# Sheet1.net
KiCad netlist of a schematic drawn in Altium Designer
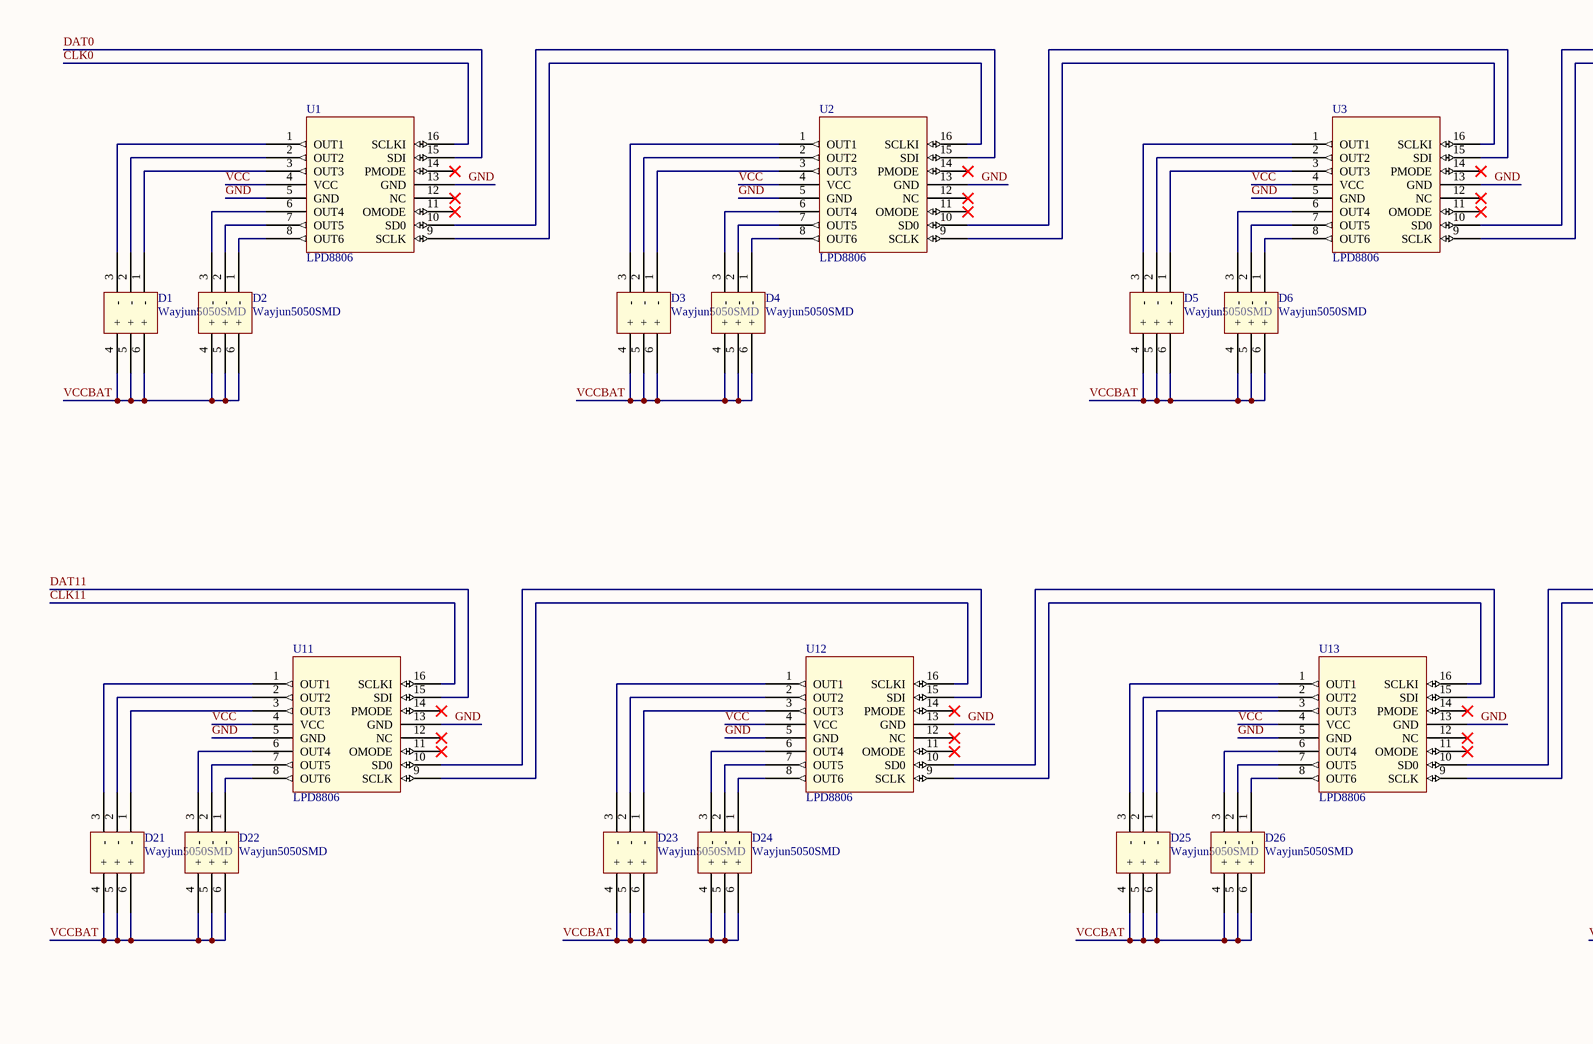
[diagram p0: Sheet1.SchDoc, top left]
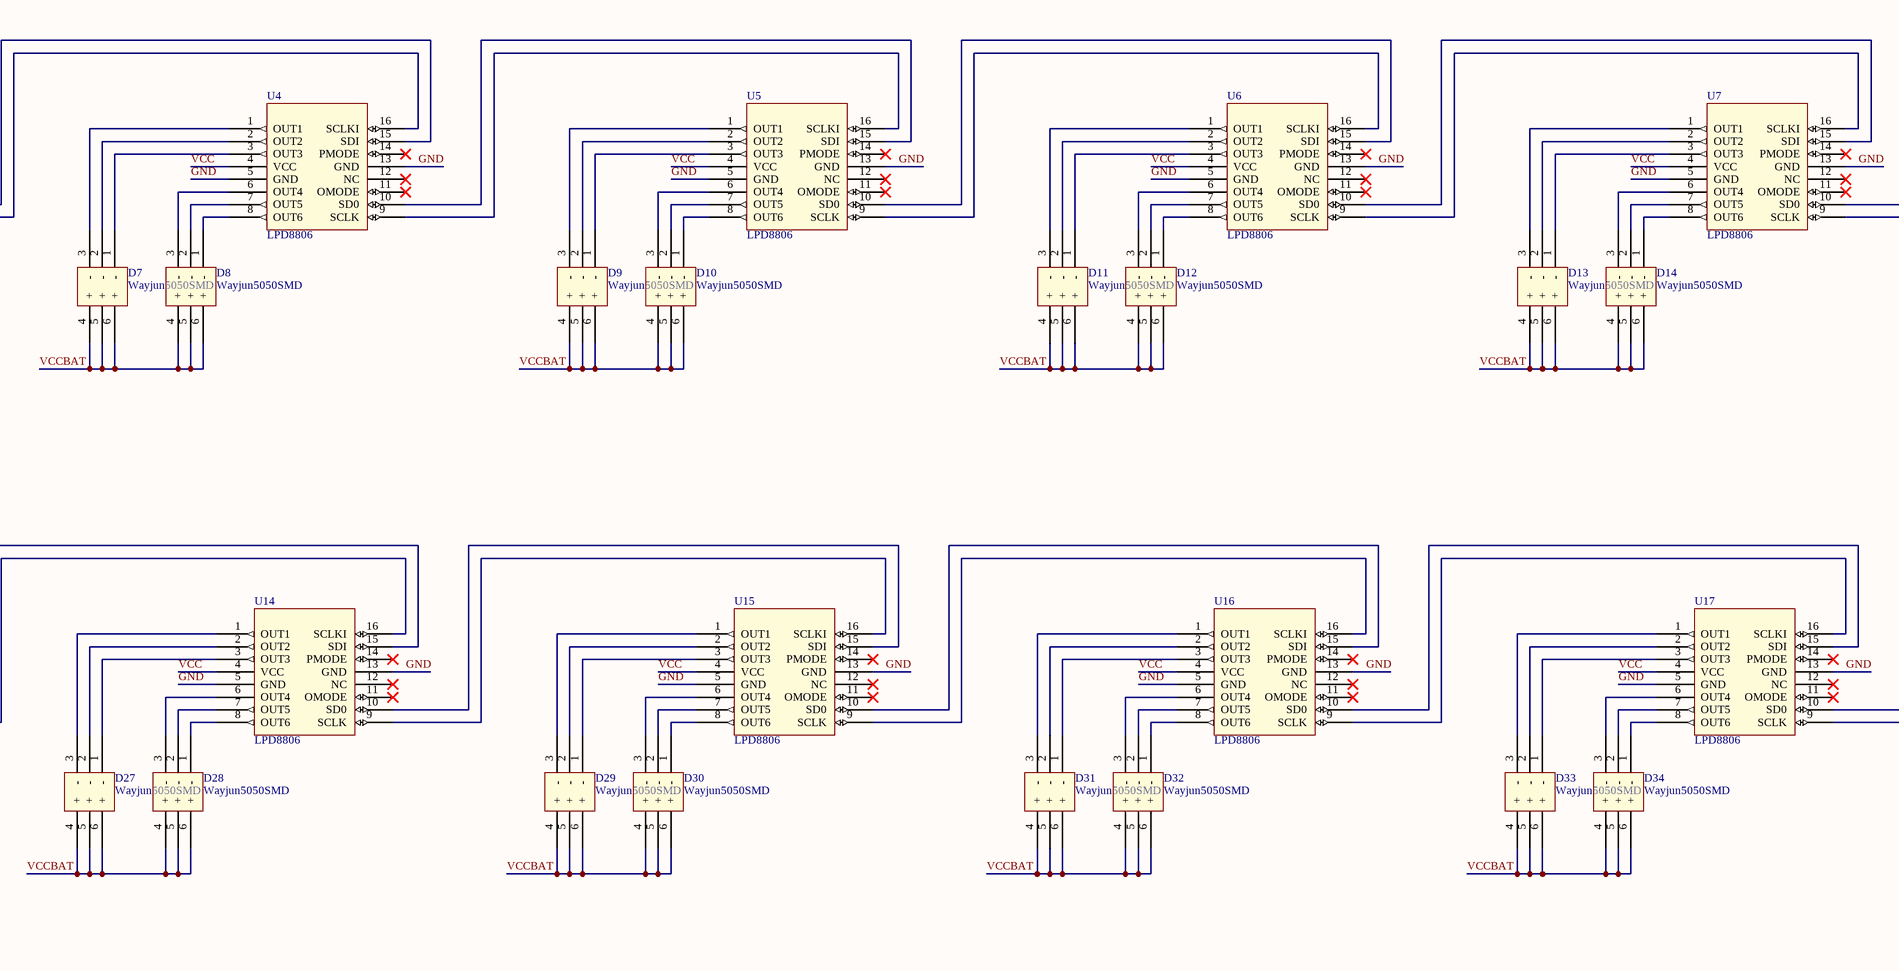
[diagram p1: Sheet1.SchDoc, top middle]
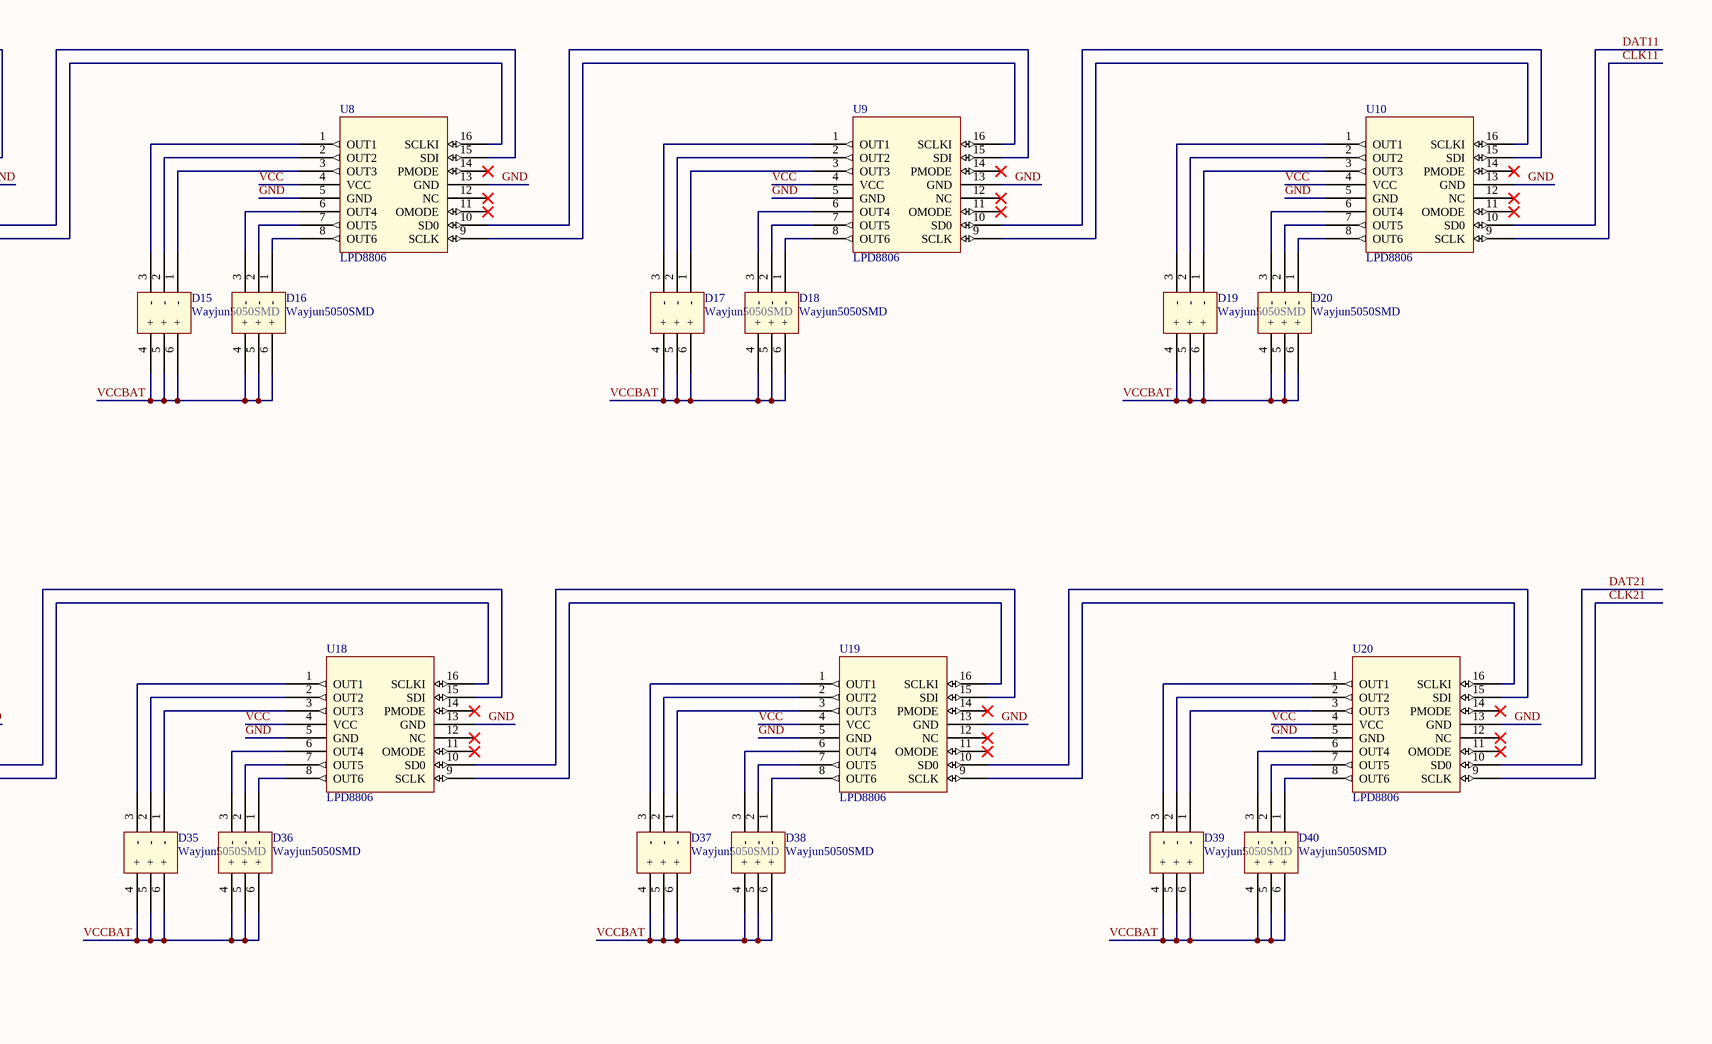
[diagram p2: Sheet1.SchDoc, top right]
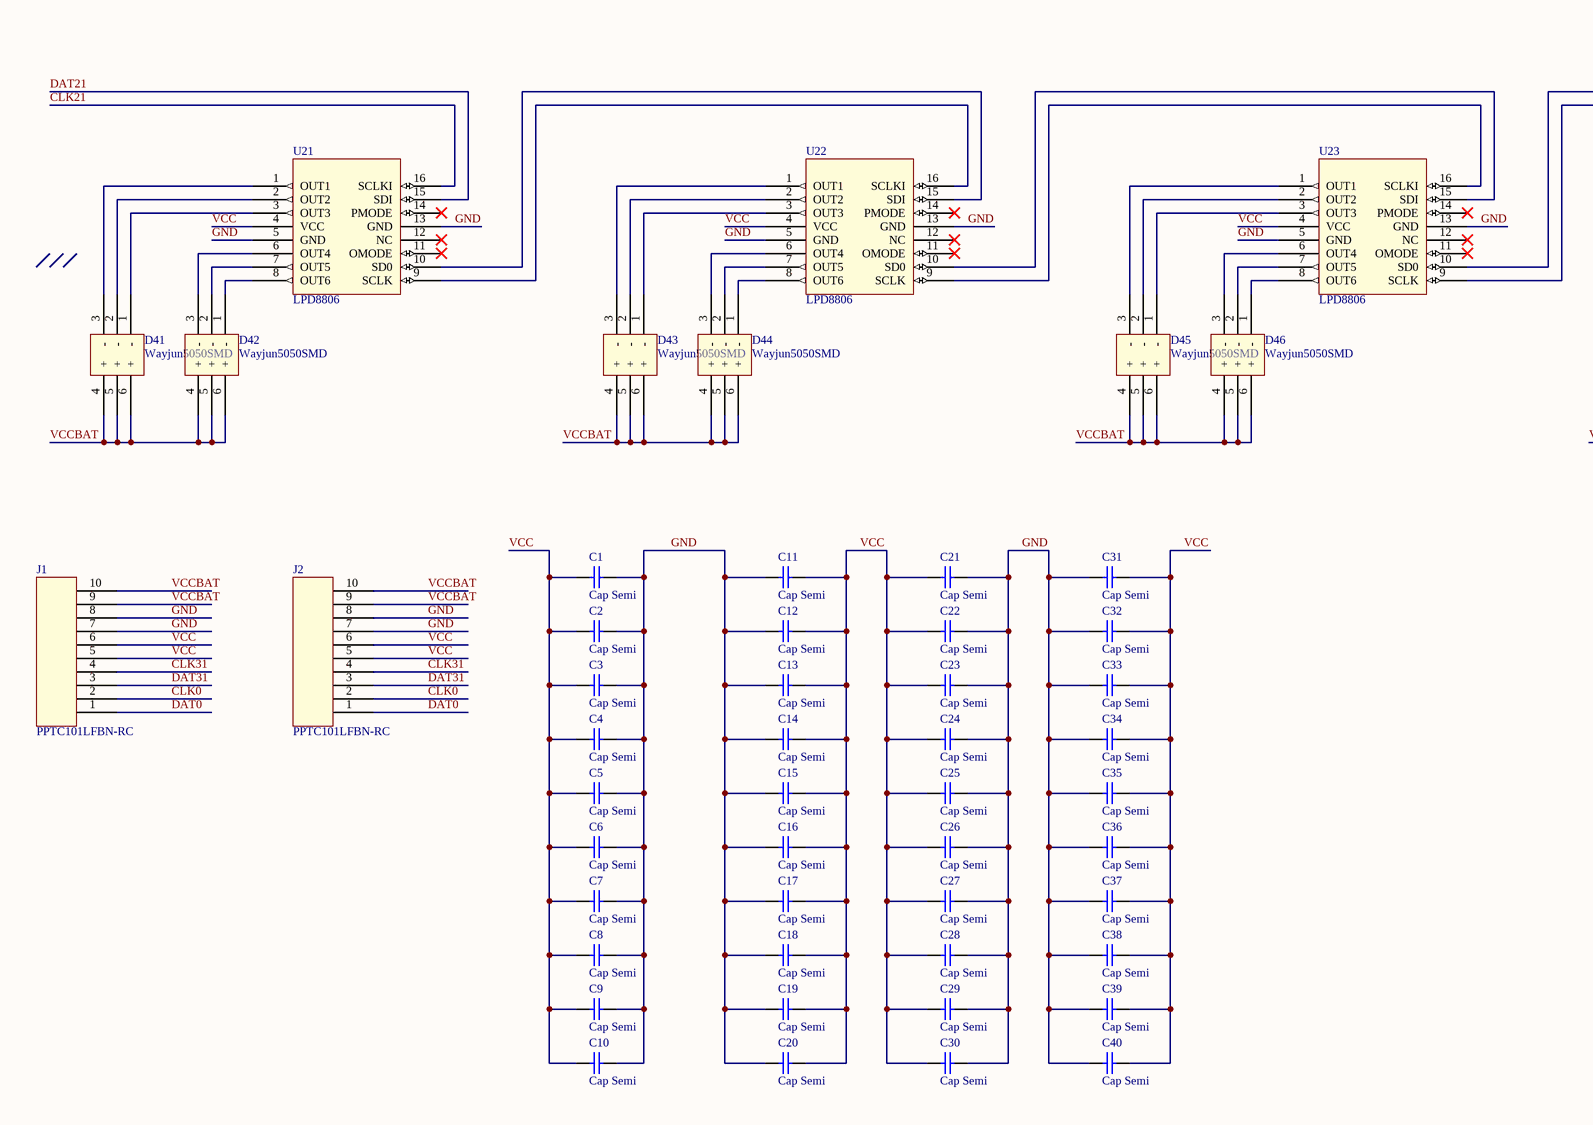
[diagram p3: Sheet1.SchDoc, bottom left]
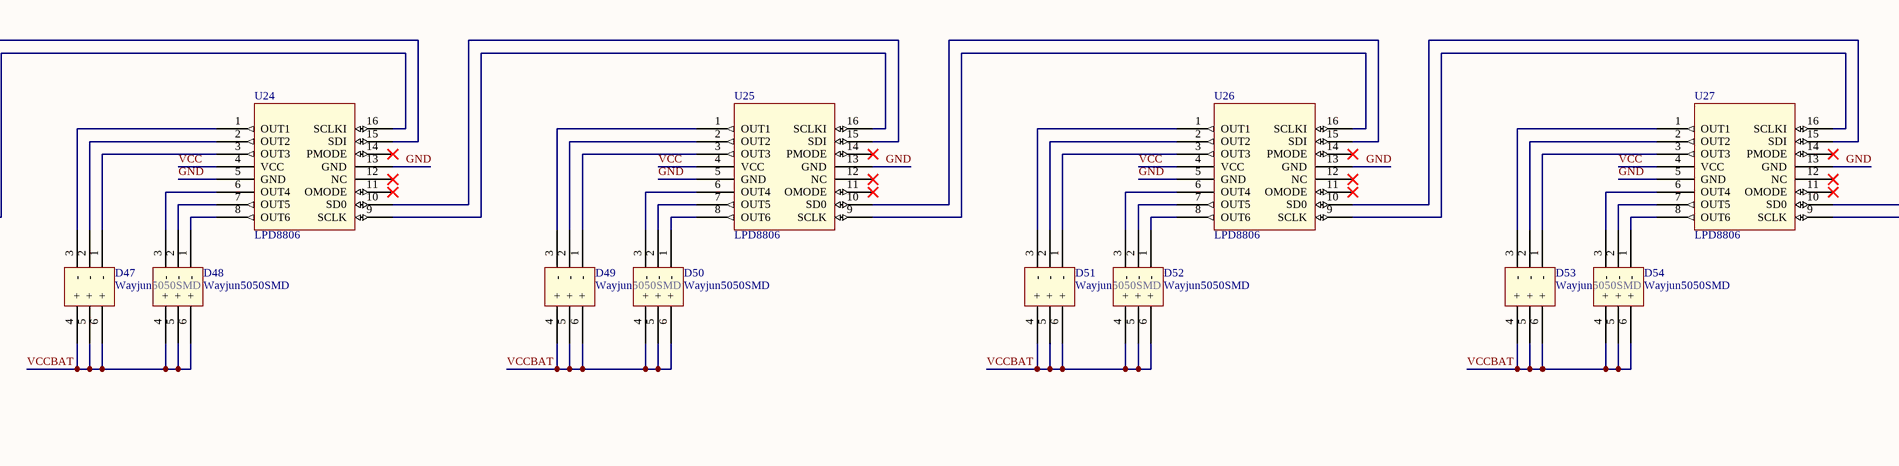
[diagram p4: Sheet1.SchDoc, bottom middle]
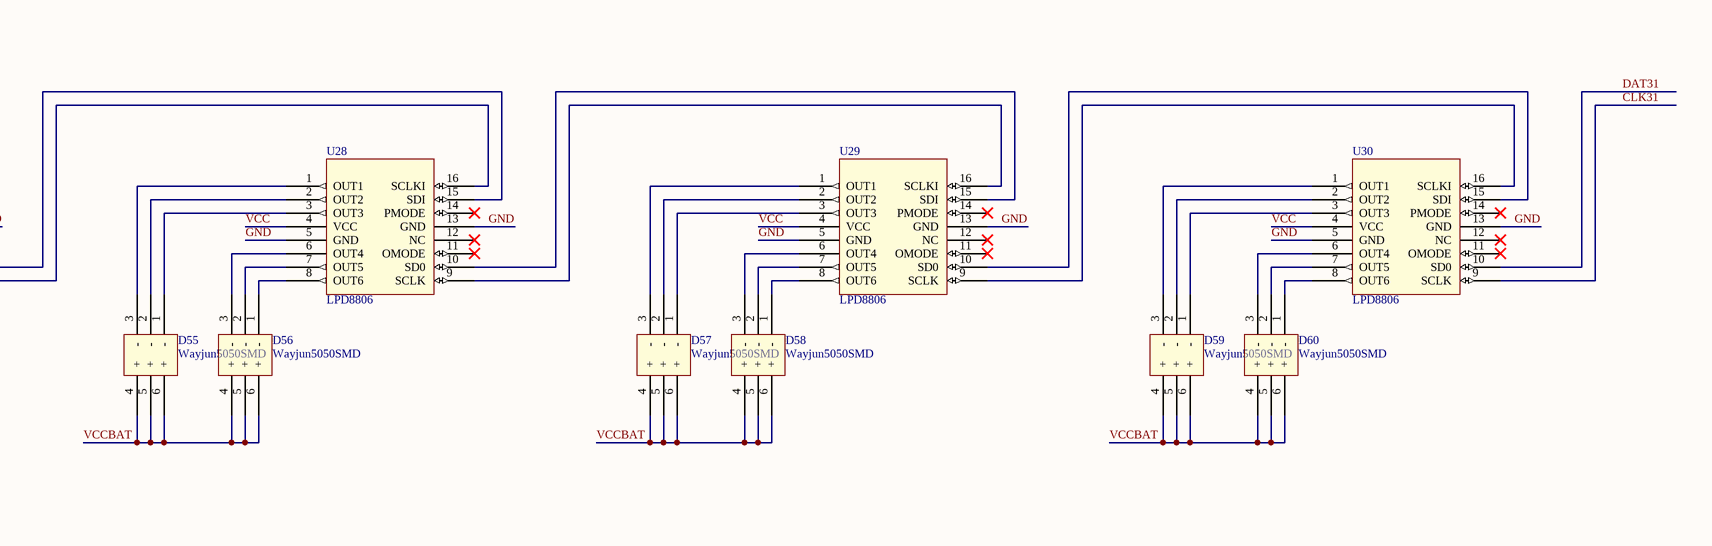
[diagram p5: Sheet1.SchDoc, bottom right]

(export (version "E")
  (design (tool "Eeschema 10.0.6"))
  (components
    (comp (ref "C1")
      (value "Cap Semi")
      (footprint "0402")
      (description "Capacitor (Semiconductor SIM Model)")
      (fields (field (name "PUBLISHER") "Altium Limited"))
      (libsource (lib "Miscellaneous Devices") (part "Cap Semi"))
    )
    (comp (ref "C2")
      (value "Cap Semi")
      (footprint "0402")
      (description "Capacitor (Semiconductor SIM Model)")
      (fields (field (name "PUBLISHER") "Altium Limited"))
      (libsource (lib "Miscellaneous Devices") (part "Cap Semi"))
    )
    (comp (ref "C3")
      (value "Cap Semi")
      (footprint "0402")
      (description "Capacitor (Semiconductor SIM Model)")
      (fields (field (name "PUBLISHER") "Altium Limited"))
      (libsource (lib "Miscellaneous Devices") (part "Cap Semi"))
    )
    (comp (ref "C4")
      (value "Cap Semi")
      (footprint "0402")
      (description "Capacitor (Semiconductor SIM Model)")
      (fields (field (name "PUBLISHER") "Altium Limited"))
      (libsource (lib "Miscellaneous Devices") (part "Cap Semi"))
    )
    (comp (ref "C5")
      (value "Cap Semi")
      (footprint "0402")
      (description "Capacitor (Semiconductor SIM Model)")
      (fields (field (name "PUBLISHER") "Altium Limited"))
      (libsource (lib "Miscellaneous Devices") (part "Cap Semi"))
    )
    (comp (ref "C6")
      (value "Cap Semi")
      (footprint "0402")
      (description "Capacitor (Semiconductor SIM Model)")
      (fields (field (name "PUBLISHER") "Altium Limited"))
      (libsource (lib "Miscellaneous Devices") (part "Cap Semi"))
    )
    (comp (ref "C7")
      (value "Cap Semi")
      (footprint "0402")
      (description "Capacitor (Semiconductor SIM Model)")
      (fields (field (name "PUBLISHER") "Altium Limited"))
      (libsource (lib "Miscellaneous Devices") (part "Cap Semi"))
    )
    (comp (ref "C8")
      (value "Cap Semi")
      (footprint "0402")
      (description "Capacitor (Semiconductor SIM Model)")
      (fields (field (name "PUBLISHER") "Altium Limited"))
      (libsource (lib "Miscellaneous Devices") (part "Cap Semi"))
    )
    (comp (ref "C9")
      (value "Cap Semi")
      (footprint "0402")
      (description "Capacitor (Semiconductor SIM Model)")
      (fields (field (name "PUBLISHER") "Altium Limited"))
      (libsource (lib "Miscellaneous Devices") (part "Cap Semi"))
    )
    (comp (ref "C10")
      (value "Cap Semi")
      (footprint "0402")
      (description "Capacitor (Semiconductor SIM Model)")
      (fields (field (name "PUBLISHER") "Altium Limited"))
      (libsource (lib "Miscellaneous Devices") (part "Cap Semi"))
    )
    (comp (ref "C11")
      (value "Cap Semi")
      (footprint "0402")
      (description "Capacitor (Semiconductor SIM Model)")
      (fields (field (name "PUBLISHER") "Altium Limited"))
      (libsource (lib "Miscellaneous Devices") (part "Cap Semi"))
    )
    (comp (ref "C12")
      (value "Cap Semi")
      (footprint "0402")
      (description "Capacitor (Semiconductor SIM Model)")
      (fields (field (name "PUBLISHER") "Altium Limited"))
      (libsource (lib "Miscellaneous Devices") (part "Cap Semi"))
    )
    (comp (ref "C13")
      (value "Cap Semi")
      (footprint "0402")
      (description "Capacitor (Semiconductor SIM Model)")
      (fields (field (name "PUBLISHER") "Altium Limited"))
      (libsource (lib "Miscellaneous Devices") (part "Cap Semi"))
    )
    (comp (ref "C14")
      (value "Cap Semi")
      (footprint "0402")
      (description "Capacitor (Semiconductor SIM Model)")
      (fields (field (name "PUBLISHER") "Altium Limited"))
      (libsource (lib "Miscellaneous Devices") (part "Cap Semi"))
    )
    (comp (ref "C15")
      (value "Cap Semi")
      (footprint "0402")
      (description "Capacitor (Semiconductor SIM Model)")
      (fields (field (name "PUBLISHER") "Altium Limited"))
      (libsource (lib "Miscellaneous Devices") (part "Cap Semi"))
    )
    (comp (ref "C16")
      (value "Cap Semi")
      (footprint "0402")
      (description "Capacitor (Semiconductor SIM Model)")
      (fields (field (name "PUBLISHER") "Altium Limited"))
      (libsource (lib "Miscellaneous Devices") (part "Cap Semi"))
    )
    (comp (ref "C17")
      (value "Cap Semi")
      (footprint "0402")
      (description "Capacitor (Semiconductor SIM Model)")
      (fields (field (name "PUBLISHER") "Altium Limited"))
      (libsource (lib "Miscellaneous Devices") (part "Cap Semi"))
    )
    (comp (ref "C18")
      (value "Cap Semi")
      (footprint "0402")
      (description "Capacitor (Semiconductor SIM Model)")
      (fields (field (name "PUBLISHER") "Altium Limited"))
      (libsource (lib "Miscellaneous Devices") (part "Cap Semi"))
    )
    (comp (ref "C19")
      (value "Cap Semi")
      (footprint "0402")
      (description "Capacitor (Semiconductor SIM Model)")
      (fields (field (name "PUBLISHER") "Altium Limited"))
      (libsource (lib "Miscellaneous Devices") (part "Cap Semi"))
    )
    (comp (ref "C20")
      (value "Cap Semi")
      (footprint "0402")
      (description "Capacitor (Semiconductor SIM Model)")
      (fields (field (name "PUBLISHER") "Altium Limited"))
      (libsource (lib "Miscellaneous Devices") (part "Cap Semi"))
    )
    (comp (ref "C21")
      (value "Cap Semi")
      (footprint "0402")
      (description "Capacitor (Semiconductor SIM Model)")
      (fields (field (name "PUBLISHER") "Altium Limited"))
      (libsource (lib "Miscellaneous Devices") (part "Cap Semi"))
    )
    (comp (ref "C22")
      (value "Cap Semi")
      (footprint "0402")
      (description "Capacitor (Semiconductor SIM Model)")
      (fields (field (name "PUBLISHER") "Altium Limited"))
      (libsource (lib "Miscellaneous Devices") (part "Cap Semi"))
    )
    (comp (ref "C23")
      (value "Cap Semi")
      (footprint "0402")
      (description "Capacitor (Semiconductor SIM Model)")
      (fields (field (name "PUBLISHER") "Altium Limited"))
      (libsource (lib "Miscellaneous Devices") (part "Cap Semi"))
    )
    (comp (ref "C24")
      (value "Cap Semi")
      (footprint "0402")
      (description "Capacitor (Semiconductor SIM Model)")
      (fields (field (name "PUBLISHER") "Altium Limited"))
      (libsource (lib "Miscellaneous Devices") (part "Cap Semi"))
    )
    (comp (ref "C25")
      (value "Cap Semi")
      (footprint "0402")
      (description "Capacitor (Semiconductor SIM Model)")
      (fields (field (name "PUBLISHER") "Altium Limited"))
      (libsource (lib "Miscellaneous Devices") (part "Cap Semi"))
    )
    (comp (ref "C26")
      (value "Cap Semi")
      (footprint "0402")
      (description "Capacitor (Semiconductor SIM Model)")
      (fields (field (name "PUBLISHER") "Altium Limited"))
      (libsource (lib "Miscellaneous Devices") (part "Cap Semi"))
    )
    (comp (ref "C27")
      (value "Cap Semi")
      (footprint "0402")
      (description "Capacitor (Semiconductor SIM Model)")
      (fields (field (name "PUBLISHER") "Altium Limited"))
      (libsource (lib "Miscellaneous Devices") (part "Cap Semi"))
    )
    (comp (ref "C28")
      (value "Cap Semi")
      (footprint "0402")
      (description "Capacitor (Semiconductor SIM Model)")
      (fields (field (name "PUBLISHER") "Altium Limited"))
      (libsource (lib "Miscellaneous Devices") (part "Cap Semi"))
    )
    (comp (ref "C29")
      (value "Cap Semi")
      (footprint "0402")
      (description "Capacitor (Semiconductor SIM Model)")
      (fields (field (name "PUBLISHER") "Altium Limited"))
      (libsource (lib "Miscellaneous Devices") (part "Cap Semi"))
    )
    (comp (ref "C30")
      (value "Cap Semi")
      (footprint "0402")
      (description "Capacitor (Semiconductor SIM Model)")
      (fields (field (name "PUBLISHER") "Altium Limited"))
      (libsource (lib "Miscellaneous Devices") (part "Cap Semi"))
    )
    (comp (ref "C31")
      (value "Cap Semi")
      (footprint "0402")
      (description "Capacitor (Semiconductor SIM Model)")
      (fields (field (name "PUBLISHER") "Altium Limited"))
      (libsource (lib "Miscellaneous Devices") (part "Cap Semi"))
    )
    (comp (ref "C32")
      (value "Cap Semi")
      (footprint "0402")
      (description "Capacitor (Semiconductor SIM Model)")
      (fields (field (name "PUBLISHER") "Altium Limited"))
      (libsource (lib "Miscellaneous Devices") (part "Cap Semi"))
    )
    (comp (ref "C33")
      (value "Cap Semi")
      (footprint "0402")
      (description "Capacitor (Semiconductor SIM Model)")
      (fields (field (name "PUBLISHER") "Altium Limited"))
      (libsource (lib "Miscellaneous Devices") (part "Cap Semi"))
    )
    (comp (ref "C34")
      (value "Cap Semi")
      (footprint "0402")
      (description "Capacitor (Semiconductor SIM Model)")
      (fields (field (name "PUBLISHER") "Altium Limited"))
      (libsource (lib "Miscellaneous Devices") (part "Cap Semi"))
    )
    (comp (ref "C35")
      (value "Cap Semi")
      (footprint "0402")
      (description "Capacitor (Semiconductor SIM Model)")
      (fields (field (name "PUBLISHER") "Altium Limited"))
      (libsource (lib "Miscellaneous Devices") (part "Cap Semi"))
    )
    (comp (ref "C36")
      (value "Cap Semi")
      (footprint "0402")
      (description "Capacitor (Semiconductor SIM Model)")
      (fields (field (name "PUBLISHER") "Altium Limited"))
      (libsource (lib "Miscellaneous Devices") (part "Cap Semi"))
    )
    (comp (ref "C37")
      (value "Cap Semi")
      (footprint "0402")
      (description "Capacitor (Semiconductor SIM Model)")
      (fields (field (name "PUBLISHER") "Altium Limited"))
      (libsource (lib "Miscellaneous Devices") (part "Cap Semi"))
    )
    (comp (ref "C38")
      (value "Cap Semi")
      (footprint "0402")
      (description "Capacitor (Semiconductor SIM Model)")
      (fields (field (name "PUBLISHER") "Altium Limited"))
      (libsource (lib "Miscellaneous Devices") (part "Cap Semi"))
    )
    (comp (ref "C39")
      (value "Cap Semi")
      (footprint "0402")
      (description "Capacitor (Semiconductor SIM Model)")
      (fields (field (name "PUBLISHER") "Altium Limited"))
      (libsource (lib "Miscellaneous Devices") (part "Cap Semi"))
    )
    (comp (ref "C40")
      (value "Cap Semi")
      (footprint "0402")
      (description "Capacitor (Semiconductor SIM Model)")
      (fields (field (name "PUBLISHER") "Altium Limited"))
      (libsource (lib "Miscellaneous Devices") (part "Cap Semi"))
    )
    (comp (ref "D1")
      (value "Wayjun5050SMD")
      (footprint "SON150P500X150_HS-7N")
      (libsource (lib "lightshow") (part "Wayjun5050SMD"))
    )
    (comp (ref "D2")
      (value "Wayjun5050SMD")
      (footprint "SON150P500X150_HS-7N")
      (libsource (lib "lightshow") (part "Wayjun5050SMD"))
    )
    (comp (ref "D3")
      (value "Wayjun5050SMD")
      (footprint "SON150P500X150_HS-7N")
      (libsource (lib "lightshow") (part "Wayjun5050SMD"))
    )
    (comp (ref "D4")
      (value "Wayjun5050SMD")
      (footprint "SON150P500X150_HS-7N")
      (libsource (lib "lightshow") (part "Wayjun5050SMD"))
    )
    (comp (ref "D5")
      (value "Wayjun5050SMD")
      (footprint "SON150P500X150_HS-7N")
      (libsource (lib "lightshow") (part "Wayjun5050SMD"))
    )
    (comp (ref "D6")
      (value "Wayjun5050SMD")
      (footprint "SON150P500X150_HS-7N")
      (libsource (lib "lightshow") (part "Wayjun5050SMD"))
    )
    (comp (ref "D7")
      (value "Wayjun5050SMD")
      (footprint "SON150P500X150_HS-7N")
      (libsource (lib "lightshow") (part "Wayjun5050SMD"))
    )
    (comp (ref "D8")
      (value "Wayjun5050SMD")
      (footprint "SON150P500X150_HS-7N")
      (libsource (lib "lightshow") (part "Wayjun5050SMD"))
    )
    (comp (ref "D9")
      (value "Wayjun5050SMD")
      (footprint "SON150P500X150_HS-7N")
      (libsource (lib "lightshow") (part "Wayjun5050SMD"))
    )
    (comp (ref "D10")
      (value "Wayjun5050SMD")
      (footprint "SON150P500X150_HS-7N")
      (libsource (lib "lightshow") (part "Wayjun5050SMD"))
    )
    (comp (ref "D11")
      (value "Wayjun5050SMD")
      (footprint "SON150P500X150_HS-7N")
      (libsource (lib "lightshow") (part "Wayjun5050SMD"))
    )
    (comp (ref "D12")
      (value "Wayjun5050SMD")
      (footprint "SON150P500X150_HS-7N")
      (libsource (lib "lightshow") (part "Wayjun5050SMD"))
    )
    (comp (ref "D13")
      (value "Wayjun5050SMD")
      (footprint "SON150P500X150_HS-7N")
      (libsource (lib "lightshow") (part "Wayjun5050SMD"))
    )
    (comp (ref "D14")
      (value "Wayjun5050SMD")
      (footprint "SON150P500X150_HS-7N")
      (libsource (lib "lightshow") (part "Wayjun5050SMD"))
    )
    (comp (ref "D15")
      (value "Wayjun5050SMD")
      (footprint "SON150P500X150_HS-7N")
      (libsource (lib "lightshow") (part "Wayjun5050SMD"))
    )
    (comp (ref "D16")
      (value "Wayjun5050SMD")
      (footprint "SON150P500X150_HS-7N")
      (libsource (lib "lightshow") (part "Wayjun5050SMD"))
    )
    (comp (ref "D17")
      (value "Wayjun5050SMD")
      (footprint "SON150P500X150_HS-7N")
      (libsource (lib "lightshow") (part "Wayjun5050SMD"))
    )
    (comp (ref "D18")
      (value "Wayjun5050SMD")
      (footprint "SON150P500X150_HS-7N")
      (libsource (lib "lightshow") (part "Wayjun5050SMD"))
    )
    (comp (ref "D19")
      (value "Wayjun5050SMD")
      (footprint "SON150P500X150_HS-7N")
      (libsource (lib "lightshow") (part "Wayjun5050SMD"))
    )
    (comp (ref "D20")
      (value "Wayjun5050SMD")
      (footprint "SON150P500X150_HS-7N")
      (libsource (lib "lightshow") (part "Wayjun5050SMD"))
    )
    (comp (ref "D21")
      (value "Wayjun5050SMD")
      (footprint "SON150P500X150_HS-7N")
      (libsource (lib "lightshow") (part "Wayjun5050SMD"))
    )
    (comp (ref "D22")
      (value "Wayjun5050SMD")
      (footprint "SON150P500X150_HS-7N")
      (libsource (lib "lightshow") (part "Wayjun5050SMD"))
    )
    (comp (ref "D23")
      (value "Wayjun5050SMD")
      (footprint "SON150P500X150_HS-7N")
      (libsource (lib "lightshow") (part "Wayjun5050SMD"))
    )
    (comp (ref "D24")
      (value "Wayjun5050SMD")
      (footprint "SON150P500X150_HS-7N")
      (libsource (lib "lightshow") (part "Wayjun5050SMD"))
    )
    (comp (ref "D25")
      (value "Wayjun5050SMD")
      (footprint "SON150P500X150_HS-7N")
      (libsource (lib "lightshow") (part "Wayjun5050SMD"))
    )
    (comp (ref "D26")
      (value "Wayjun5050SMD")
      (footprint "SON150P500X150_HS-7N")
      (libsource (lib "lightshow") (part "Wayjun5050SMD"))
    )
    (comp (ref "D27")
      (value "Wayjun5050SMD")
      (footprint "SON150P500X150_HS-7N")
      (libsource (lib "lightshow") (part "Wayjun5050SMD"))
    )
    (comp (ref "D28")
      (value "Wayjun5050SMD")
      (footprint "SON150P500X150_HS-7N")
      (libsource (lib "lightshow") (part "Wayjun5050SMD"))
    )
    (comp (ref "D29")
      (value "Wayjun5050SMD")
      (footprint "SON150P500X150_HS-7N")
      (libsource (lib "lightshow") (part "Wayjun5050SMD"))
    )
    (comp (ref "D30")
      (value "Wayjun5050SMD")
      (footprint "SON150P500X150_HS-7N")
      (libsource (lib "lightshow") (part "Wayjun5050SMD"))
    )
    (comp (ref "D31")
      (value "Wayjun5050SMD")
      (footprint "SON150P500X150_HS-7N")
      (libsource (lib "lightshow") (part "Wayjun5050SMD"))
    )
    (comp (ref "D32")
      (value "Wayjun5050SMD")
      (footprint "SON150P500X150_HS-7N")
      (libsource (lib "lightshow") (part "Wayjun5050SMD"))
    )
    (comp (ref "D33")
      (value "Wayjun5050SMD")
      (footprint "SON150P500X150_HS-7N")
      (libsource (lib "lightshow") (part "Wayjun5050SMD"))
    )
    (comp (ref "D34")
      (value "Wayjun5050SMD")
      (footprint "SON150P500X150_HS-7N")
      (libsource (lib "lightshow") (part "Wayjun5050SMD"))
    )
    (comp (ref "D35")
      (value "Wayjun5050SMD")
      (footprint "SON150P500X150_HS-7N")
      (libsource (lib "lightshow") (part "Wayjun5050SMD"))
    )
    (comp (ref "D36")
      (value "Wayjun5050SMD")
      (footprint "SON150P500X150_HS-7N")
      (libsource (lib "lightshow") (part "Wayjun5050SMD"))
    )
    (comp (ref "D37")
      (value "Wayjun5050SMD")
      (footprint "SON150P500X150_HS-7N")
      (libsource (lib "lightshow") (part "Wayjun5050SMD"))
    )
    (comp (ref "D38")
      (value "Wayjun5050SMD")
      (footprint "SON150P500X150_HS-7N")
      (libsource (lib "lightshow") (part "Wayjun5050SMD"))
    )
    (comp (ref "D39")
      (value "Wayjun5050SMD")
      (footprint "SON150P500X150_HS-7N")
      (libsource (lib "lightshow") (part "Wayjun5050SMD"))
    )
    (comp (ref "D40")
      (value "Wayjun5050SMD")
      (footprint "SON150P500X150_HS-7N")
      (libsource (lib "lightshow") (part "Wayjun5050SMD"))
    )
    (comp (ref "D41")
      (value "Wayjun5050SMD")
      (footprint "SON150P500X150_HS-7N")
      (libsource (lib "lightshow") (part "Wayjun5050SMD"))
    )
    (comp (ref "D42")
      (value "Wayjun5050SMD")
      (footprint "SON150P500X150_HS-7N")
      (libsource (lib "lightshow") (part "Wayjun5050SMD"))
    )
    (comp (ref "D43")
      (value "Wayjun5050SMD")
      (footprint "SON150P500X150_HS-7N")
      (libsource (lib "lightshow") (part "Wayjun5050SMD"))
    )
    (comp (ref "D44")
      (value "Wayjun5050SMD")
      (footprint "SON150P500X150_HS-7N")
      (libsource (lib "lightshow") (part "Wayjun5050SMD"))
    )
    (comp (ref "D45")
      (value "Wayjun5050SMD")
      (footprint "SON150P500X150_HS-7N")
      (libsource (lib "lightshow") (part "Wayjun5050SMD"))
    )
    (comp (ref "D46")
      (value "Wayjun5050SMD")
      (footprint "SON150P500X150_HS-7N")
      (libsource (lib "lightshow") (part "Wayjun5050SMD"))
    )
    (comp (ref "D47")
      (value "Wayjun5050SMD")
      (footprint "SON150P500X150_HS-7N")
      (libsource (lib "lightshow") (part "Wayjun5050SMD"))
    )
    (comp (ref "D48")
      (value "Wayjun5050SMD")
      (footprint "SON150P500X150_HS-7N")
      (libsource (lib "lightshow") (part "Wayjun5050SMD"))
    )
    (comp (ref "D49")
      (value "Wayjun5050SMD")
      (footprint "SON150P500X150_HS-7N")
      (libsource (lib "lightshow") (part "Wayjun5050SMD"))
    )
    (comp (ref "D50")
      (value "Wayjun5050SMD")
      (footprint "SON150P500X150_HS-7N")
      (libsource (lib "lightshow") (part "Wayjun5050SMD"))
    )
    (comp (ref "D51")
      (value "Wayjun5050SMD")
      (footprint "SON150P500X150_HS-7N")
      (libsource (lib "lightshow") (part "Wayjun5050SMD"))
    )
    (comp (ref "D52")
      (value "Wayjun5050SMD")
      (footprint "SON150P500X150_HS-7N")
      (libsource (lib "lightshow") (part "Wayjun5050SMD"))
    )
    (comp (ref "D53")
      (value "Wayjun5050SMD")
      (footprint "SON150P500X150_HS-7N")
      (libsource (lib "lightshow") (part "Wayjun5050SMD"))
    )
    (comp (ref "D54")
      (value "Wayjun5050SMD")
      (footprint "SON150P500X150_HS-7N")
      (libsource (lib "lightshow") (part "Wayjun5050SMD"))
    )
    (comp (ref "D55")
      (value "Wayjun5050SMD")
      (footprint "SON150P500X150_HS-7N")
      (libsource (lib "lightshow") (part "Wayjun5050SMD"))
    )
    (comp (ref "D56")
      (value "Wayjun5050SMD")
      (footprint "SON150P500X150_HS-7N")
      (libsource (lib "lightshow") (part "Wayjun5050SMD"))
    )
    (comp (ref "D57")
      (value "Wayjun5050SMD")
      (footprint "SON150P500X150_HS-7N")
      (libsource (lib "lightshow") (part "Wayjun5050SMD"))
    )
    (comp (ref "D58")
      (value "Wayjun5050SMD")
      (footprint "SON150P500X150_HS-7N")
      (libsource (lib "lightshow") (part "Wayjun5050SMD"))
    )
    (comp (ref "D59")
      (value "Wayjun5050SMD")
      (footprint "SON150P500X150_HS-7N")
      (libsource (lib "lightshow") (part "Wayjun5050SMD"))
    )
    (comp (ref "D60")
      (value "Wayjun5050SMD")
      (footprint "SON150P500X150_HS-7N")
      (libsource (lib "lightshow") (part "Wayjun5050SMD"))
    )
    (comp (ref "J1")
      (value "PPTC101LFBN-RC")
      (footprint "PPTC101LFBN-RC")
      (description "Sullins PPTC101LFBN-RC 10 Position Header Connector 0.100\" (2.54mm) Through Hole Tin")
      (libsource (lib "lightshow") (part "PPTC101LFBN-RC"))
    )
    (comp (ref "J2")
      (value "PPTC101LFBN-RC")
      (footprint "PPTC101LFBN-RC")
      (description "Sullins PPTC101LFBN-RC 10 Position Header Connector 0.100\" (2.54mm) Through Hole Tin")
      (libsource (lib "lightshow") (part "PPTC101LFBN-RC"))
    )
    (comp (ref "U1")
      (value "LPD8806")
      (footprint "SOP127P600-8N")
      (description "LPD8806 LED Driver")
      (libsource (lib "lightshow") (part "LPD8806"))
    )
    (comp (ref "U2")
      (value "LPD8806")
      (footprint "SOP127P600-8N")
      (description "LPD8806 LED Driver")
      (libsource (lib "lightshow") (part "LPD8806"))
    )
    (comp (ref "U3")
      (value "LPD8806")
      (footprint "SOP127P600-8N")
      (description "LPD8806 LED Driver")
      (libsource (lib "lightshow") (part "LPD8806"))
    )
    (comp (ref "U4")
      (value "LPD8806")
      (footprint "SOP127P600-8N")
      (description "LPD8806 LED Driver")
      (libsource (lib "lightshow") (part "LPD8806"))
    )
    (comp (ref "U5")
      (value "LPD8806")
      (footprint "SOP127P600-8N")
      (description "LPD8806 LED Driver")
      (libsource (lib "lightshow") (part "LPD8806"))
    )
    (comp (ref "U6")
      (value "LPD8806")
      (footprint "SOP127P600-8N")
      (description "LPD8806 LED Driver")
      (libsource (lib "lightshow") (part "LPD8806"))
    )
    (comp (ref "U7")
      (value "LPD8806")
      (footprint "SOP127P600-8N")
      (description "LPD8806 LED Driver")
      (libsource (lib "lightshow") (part "LPD8806"))
    )
    (comp (ref "U8")
      (value "LPD8806")
      (footprint "SOP127P600-8N")
      (description "LPD8806 LED Driver")
      (libsource (lib "lightshow") (part "LPD8806"))
    )
    (comp (ref "U9")
      (value "LPD8806")
      (footprint "SOP127P600-8N")
      (description "LPD8806 LED Driver")
      (libsource (lib "lightshow") (part "LPD8806"))
    )
    (comp (ref "U10")
      (value "LPD8806")
      (footprint "SOP127P600-8N")
      (description "LPD8806 LED Driver")
      (libsource (lib "lightshow") (part "LPD8806"))
    )
    (comp (ref "U11")
      (value "LPD8806")
      (footprint "SOP127P600-8N")
      (description "LPD8806 LED Driver")
      (libsource (lib "lightshow") (part "LPD8806"))
    )
    (comp (ref "U12")
      (value "LPD8806")
      (footprint "SOP127P600-8N")
      (description "LPD8806 LED Driver")
      (libsource (lib "lightshow") (part "LPD8806"))
    )
    (comp (ref "U13")
      (value "LPD8806")
      (footprint "SOP127P600-8N")
      (description "LPD8806 LED Driver")
      (libsource (lib "lightshow") (part "LPD8806"))
    )
    (comp (ref "U14")
      (value "LPD8806")
      (footprint "SOP127P600-8N")
      (description "LPD8806 LED Driver")
      (libsource (lib "lightshow") (part "LPD8806"))
    )
    (comp (ref "U15")
      (value "LPD8806")
      (footprint "SOP127P600-8N")
      (description "LPD8806 LED Driver")
      (libsource (lib "lightshow") (part "LPD8806"))
    )
    (comp (ref "U16")
      (value "LPD8806")
      (footprint "SOP127P600-8N")
      (description "LPD8806 LED Driver")
      (libsource (lib "lightshow") (part "LPD8806"))
    )
    (comp (ref "U17")
      (value "LPD8806")
      (footprint "SOP127P600-8N")
      (description "LPD8806 LED Driver")
      (libsource (lib "lightshow") (part "LPD8806"))
    )
    (comp (ref "U18")
      (value "LPD8806")
      (footprint "SOP127P600-8N")
      (description "LPD8806 LED Driver")
      (libsource (lib "lightshow") (part "LPD8806"))
    )
    (comp (ref "U19")
      (value "LPD8806")
      (footprint "SOP127P600-8N")
      (description "LPD8806 LED Driver")
      (libsource (lib "lightshow") (part "LPD8806"))
    )
    (comp (ref "U20")
      (value "LPD8806")
      (footprint "SOP127P600-8N")
      (description "LPD8806 LED Driver")
      (libsource (lib "lightshow") (part "LPD8806"))
    )
    (comp (ref "U21")
      (value "LPD8806")
      (footprint "SOP127P600-8N")
      (description "LPD8806 LED Driver")
      (libsource (lib "lightshow") (part "LPD8806"))
    )
    (comp (ref "U22")
      (value "LPD8806")
      (footprint "SOP127P600-8N")
      (description "LPD8806 LED Driver")
      (libsource (lib "lightshow") (part "LPD8806"))
    )
    (comp (ref "U23")
      (value "LPD8806")
      (footprint "SOP127P600-8N")
      (description "LPD8806 LED Driver")
      (libsource (lib "lightshow") (part "LPD8806"))
    )
    (comp (ref "U24")
      (value "LPD8806")
      (footprint "SOP127P600-8N")
      (description "LPD8806 LED Driver")
      (libsource (lib "lightshow") (part "LPD8806"))
    )
    (comp (ref "U25")
      (value "LPD8806")
      (footprint "SOP127P600-8N")
      (description "LPD8806 LED Driver")
      (libsource (lib "lightshow") (part "LPD8806"))
    )
    (comp (ref "U26")
      (value "LPD8806")
      (footprint "SOP127P600-8N")
      (description "LPD8806 LED Driver")
      (libsource (lib "lightshow") (part "LPD8806"))
    )
    (comp (ref "U27")
      (value "LPD8806")
      (footprint "SOP127P600-8N")
      (description "LPD8806 LED Driver")
      (libsource (lib "lightshow") (part "LPD8806"))
    )
    (comp (ref "U28")
      (value "LPD8806")
      (footprint "SOP127P600-8N")
      (description "LPD8806 LED Driver")
      (libsource (lib "lightshow") (part "LPD8806"))
    )
    (comp (ref "U29")
      (value "LPD8806")
      (footprint "SOP127P600-8N")
      (description "LPD8806 LED Driver")
      (libsource (lib "lightshow") (part "LPD8806"))
    )
    (comp (ref "U30")
      (value "LPD8806")
      (footprint "SOP127P600-8N")
      (description "LPD8806 LED Driver")
      (libsource (lib "lightshow") (part "LPD8806"))
    )
  )
  (nets
    (net (code "1") (name "/CLK0") (class "Default")
      (node (ref "J1") (pin "2") (pintype "passive"))
      (node (ref "J2") (pin "2") (pintype "passive"))
      (node (ref "U1") (pin "16") (pinfunction "SCLKI_16") (pintype "bidirectional"))
    )
    (net (code "2") (name "/CLK11") (class "Default")
      (node (ref "U10") (pin "9") (pinfunction "SCLK_9") (pintype "bidirectional"))
      (node (ref "U11") (pin "16") (pinfunction "SCLKI_16") (pintype "bidirectional"))
    )
    (net (code "3") (name "/CLK21") (class "Default")
      (node (ref "U20") (pin "9") (pinfunction "SCLK_9") (pintype "bidirectional"))
      (node (ref "U21") (pin "16") (pinfunction "SCLKI_16") (pintype "bidirectional"))
    )
    (net (code "4") (name "/CLK31") (class "Default")
      (node (ref "J1") (pin "4") (pintype "passive"))
      (node (ref "J2") (pin "4") (pintype "passive"))
      (node (ref "U30") (pin "9") (pinfunction "SCLK_9") (pintype "bidirectional"))
    )
    (net (code "5") (name "/DAT0") (class "Default")
      (node (ref "J1") (pin "1") (pintype "passive"))
      (node (ref "J2") (pin "1") (pintype "passive"))
      (node (ref "U1") (pin "15") (pinfunction "SDI_15") (pintype "bidirectional"))
    )
    (net (code "6") (name "/DAT11") (class "Default")
      (node (ref "U10") (pin "10") (pinfunction "SD0_10") (pintype "bidirectional"))
      (node (ref "U11") (pin "15") (pinfunction "SDI_15") (pintype "bidirectional"))
    )
    (net (code "7") (name "/DAT21") (class "Default")
      (node (ref "U20") (pin "10") (pinfunction "SD0_10") (pintype "bidirectional"))
      (node (ref "U21") (pin "15") (pinfunction "SDI_15") (pintype "bidirectional"))
    )
    (net (code "8") (name "/DAT31") (class "Default")
      (node (ref "J1") (pin "3") (pintype "passive"))
      (node (ref "J2") (pin "3") (pintype "passive"))
      (node (ref "U30") (pin "10") (pinfunction "SD0_10") (pintype "bidirectional"))
    )
    (net (code "9") (name "/GND") (class "Default")
      (node (ref "C1") (pin "2") (pinfunction "2_2") (pintype "passive"))
      (node (ref "C10") (pin "2") (pinfunction "2_2") (pintype "passive"))
      (node (ref "C11") (pin "1") (pinfunction "1_1") (pintype "passive"))
      (node (ref "C12") (pin "1") (pinfunction "1_1") (pintype "passive"))
      (node (ref "C13") (pin "1") (pinfunction "1_1") (pintype "passive"))
      (node (ref "C14") (pin "1") (pinfunction "1_1") (pintype "passive"))
      (node (ref "C15") (pin "1") (pinfunction "1_1") (pintype "passive"))
      (node (ref "C16") (pin "1") (pinfunction "1_1") (pintype "passive"))
      (node (ref "C17") (pin "1") (pinfunction "1_1") (pintype "passive"))
      (node (ref "C18") (pin "1") (pinfunction "1_1") (pintype "passive"))
      (node (ref "C19") (pin "1") (pinfunction "1_1") (pintype "passive"))
      (node (ref "C2") (pin "2") (pinfunction "2_2") (pintype "passive"))
      (node (ref "C20") (pin "1") (pinfunction "1_1") (pintype "passive"))
      (node (ref "C21") (pin "2") (pinfunction "2_2") (pintype "passive"))
      (node (ref "C22") (pin "2") (pinfunction "2_2") (pintype "passive"))
      (node (ref "C23") (pin "2") (pinfunction "2_2") (pintype "passive"))
      (node (ref "C24") (pin "2") (pinfunction "2_2") (pintype "passive"))
      (node (ref "C25") (pin "2") (pinfunction "2_2") (pintype "passive"))
      (node (ref "C26") (pin "2") (pinfunction "2_2") (pintype "passive"))
      (node (ref "C27") (pin "2") (pinfunction "2_2") (pintype "passive"))
      (node (ref "C28") (pin "2") (pinfunction "2_2") (pintype "passive"))
      (node (ref "C29") (pin "2") (pinfunction "2_2") (pintype "passive"))
      (node (ref "C3") (pin "2") (pinfunction "2_2") (pintype "passive"))
      (node (ref "C30") (pin "2") (pinfunction "2_2") (pintype "passive"))
      (node (ref "C31") (pin "1") (pinfunction "1_1") (pintype "passive"))
      (node (ref "C32") (pin "1") (pinfunction "1_1") (pintype "passive"))
      (node (ref "C33") (pin "1") (pinfunction "1_1") (pintype "passive"))
      (node (ref "C34") (pin "1") (pinfunction "1_1") (pintype "passive"))
      (node (ref "C35") (pin "1") (pinfunction "1_1") (pintype "passive"))
      (node (ref "C36") (pin "1") (pinfunction "1_1") (pintype "passive"))
      (node (ref "C37") (pin "1") (pinfunction "1_1") (pintype "passive"))
      (node (ref "C38") (pin "1") (pinfunction "1_1") (pintype "passive"))
      (node (ref "C39") (pin "1") (pinfunction "1_1") (pintype "passive"))
      (node (ref "C4") (pin "2") (pinfunction "2_2") (pintype "passive"))
      (node (ref "C40") (pin "1") (pinfunction "1_1") (pintype "passive"))
      (node (ref "C5") (pin "2") (pinfunction "2_2") (pintype "passive"))
      (node (ref "C6") (pin "2") (pinfunction "2_2") (pintype "passive"))
      (node (ref "C7") (pin "2") (pinfunction "2_2") (pintype "passive"))
      (node (ref "C8") (pin "2") (pinfunction "2_2") (pintype "passive"))
      (node (ref "C9") (pin "2") (pinfunction "2_2") (pintype "passive"))
      (node (ref "J1") (pin "7") (pintype "passive"))
      (node (ref "J1") (pin "8") (pintype "passive"))
      (node (ref "J2") (pin "7") (pintype "passive"))
      (node (ref "J2") (pin "8") (pintype "passive"))
      (node (ref "U1") (pin "13") (pinfunction "GND_13") (pintype "power_in"))
      (node (ref "U1") (pin "5") (pinfunction "GND_5") (pintype "power_in"))
      (node (ref "U10") (pin "13") (pinfunction "GND_13") (pintype "power_in"))
      (node (ref "U10") (pin "5") (pinfunction "GND_5") (pintype "power_in"))
      (node (ref "U11") (pin "13") (pinfunction "GND_13") (pintype "power_in"))
      (node (ref "U11") (pin "5") (pinfunction "GND_5") (pintype "power_in"))
      (node (ref "U12") (pin "13") (pinfunction "GND_13") (pintype "power_in"))
      (node (ref "U12") (pin "5") (pinfunction "GND_5") (pintype "power_in"))
      (node (ref "U13") (pin "13") (pinfunction "GND_13") (pintype "power_in"))
      (node (ref "U13") (pin "5") (pinfunction "GND_5") (pintype "power_in"))
      (node (ref "U14") (pin "13") (pinfunction "GND_13") (pintype "power_in"))
      (node (ref "U14") (pin "5") (pinfunction "GND_5") (pintype "power_in"))
      (node (ref "U15") (pin "13") (pinfunction "GND_13") (pintype "power_in"))
      (node (ref "U15") (pin "5") (pinfunction "GND_5") (pintype "power_in"))
      (node (ref "U16") (pin "13") (pinfunction "GND_13") (pintype "power_in"))
      (node (ref "U16") (pin "5") (pinfunction "GND_5") (pintype "power_in"))
      (node (ref "U17") (pin "13") (pinfunction "GND_13") (pintype "power_in"))
      (node (ref "U17") (pin "5") (pinfunction "GND_5") (pintype "power_in"))
      (node (ref "U18") (pin "13") (pinfunction "GND_13") (pintype "power_in"))
      (node (ref "U18") (pin "5") (pinfunction "GND_5") (pintype "power_in"))
      (node (ref "U19") (pin "13") (pinfunction "GND_13") (pintype "power_in"))
      (node (ref "U19") (pin "5") (pinfunction "GND_5") (pintype "power_in"))
      (node (ref "U2") (pin "13") (pinfunction "GND_13") (pintype "power_in"))
      (node (ref "U2") (pin "5") (pinfunction "GND_5") (pintype "power_in"))
      (node (ref "U20") (pin "13") (pinfunction "GND_13") (pintype "power_in"))
      (node (ref "U20") (pin "5") (pinfunction "GND_5") (pintype "power_in"))
      (node (ref "U21") (pin "13") (pinfunction "GND_13") (pintype "power_in"))
      (node (ref "U21") (pin "5") (pinfunction "GND_5") (pintype "power_in"))
      (node (ref "U22") (pin "13") (pinfunction "GND_13") (pintype "power_in"))
      (node (ref "U22") (pin "5") (pinfunction "GND_5") (pintype "power_in"))
      (node (ref "U23") (pin "13") (pinfunction "GND_13") (pintype "power_in"))
      (node (ref "U23") (pin "5") (pinfunction "GND_5") (pintype "power_in"))
      (node (ref "U24") (pin "13") (pinfunction "GND_13") (pintype "power_in"))
      (node (ref "U24") (pin "5") (pinfunction "GND_5") (pintype "power_in"))
      (node (ref "U25") (pin "13") (pinfunction "GND_13") (pintype "power_in"))
      (node (ref "U25") (pin "5") (pinfunction "GND_5") (pintype "power_in"))
      (node (ref "U26") (pin "13") (pinfunction "GND_13") (pintype "power_in"))
      (node (ref "U26") (pin "5") (pinfunction "GND_5") (pintype "power_in"))
      (node (ref "U27") (pin "13") (pinfunction "GND_13") (pintype "power_in"))
      (node (ref "U27") (pin "5") (pinfunction "GND_5") (pintype "power_in"))
      (node (ref "U28") (pin "13") (pinfunction "GND_13") (pintype "power_in"))
      (node (ref "U28") (pin "5") (pinfunction "GND_5") (pintype "power_in"))
      (node (ref "U29") (pin "13") (pinfunction "GND_13") (pintype "power_in"))
      (node (ref "U29") (pin "5") (pinfunction "GND_5") (pintype "power_in"))
      (node (ref "U3") (pin "13") (pinfunction "GND_13") (pintype "power_in"))
      (node (ref "U3") (pin "5") (pinfunction "GND_5") (pintype "power_in"))
      (node (ref "U30") (pin "13") (pinfunction "GND_13") (pintype "power_in"))
      (node (ref "U30") (pin "5") (pinfunction "GND_5") (pintype "power_in"))
      (node (ref "U4") (pin "13") (pinfunction "GND_13") (pintype "power_in"))
      (node (ref "U4") (pin "5") (pinfunction "GND_5") (pintype "power_in"))
      (node (ref "U5") (pin "13") (pinfunction "GND_13") (pintype "power_in"))
      (node (ref "U5") (pin "5") (pinfunction "GND_5") (pintype "power_in"))
      (node (ref "U6") (pin "13") (pinfunction "GND_13") (pintype "power_in"))
      (node (ref "U6") (pin "5") (pinfunction "GND_5") (pintype "power_in"))
      (node (ref "U7") (pin "13") (pinfunction "GND_13") (pintype "power_in"))
      (node (ref "U7") (pin "5") (pinfunction "GND_5") (pintype "power_in"))
      (node (ref "U8") (pin "13") (pinfunction "GND_13") (pintype "power_in"))
      (node (ref "U8") (pin "5") (pinfunction "GND_5") (pintype "power_in"))
      (node (ref "U9") (pin "13") (pinfunction "GND_13") (pintype "power_in"))
      (node (ref "U9") (pin "5") (pinfunction "GND_5") (pintype "power_in"))
    )
    (net (code "10") (name "/VCC") (class "Default")
      (node (ref "C1") (pin "1") (pinfunction "1_1") (pintype "passive"))
      (node (ref "C10") (pin "1") (pinfunction "1_1") (pintype "passive"))
      (node (ref "C11") (pin "2") (pinfunction "2_2") (pintype "passive"))
      (node (ref "C12") (pin "2") (pinfunction "2_2") (pintype "passive"))
      (node (ref "C13") (pin "2") (pinfunction "2_2") (pintype "passive"))
      (node (ref "C14") (pin "2") (pinfunction "2_2") (pintype "passive"))
      (node (ref "C15") (pin "2") (pinfunction "2_2") (pintype "passive"))
      (node (ref "C16") (pin "2") (pinfunction "2_2") (pintype "passive"))
      (node (ref "C17") (pin "2") (pinfunction "2_2") (pintype "passive"))
      (node (ref "C18") (pin "2") (pinfunction "2_2") (pintype "passive"))
      (node (ref "C19") (pin "2") (pinfunction "2_2") (pintype "passive"))
      (node (ref "C2") (pin "1") (pinfunction "1_1") (pintype "passive"))
      (node (ref "C20") (pin "2") (pinfunction "2_2") (pintype "passive"))
      (node (ref "C21") (pin "1") (pinfunction "1_1") (pintype "passive"))
      (node (ref "C22") (pin "1") (pinfunction "1_1") (pintype "passive"))
      (node (ref "C23") (pin "1") (pinfunction "1_1") (pintype "passive"))
      (node (ref "C24") (pin "1") (pinfunction "1_1") (pintype "passive"))
      (node (ref "C25") (pin "1") (pinfunction "1_1") (pintype "passive"))
      (node (ref "C26") (pin "1") (pinfunction "1_1") (pintype "passive"))
      (node (ref "C27") (pin "1") (pinfunction "1_1") (pintype "passive"))
      (node (ref "C28") (pin "1") (pinfunction "1_1") (pintype "passive"))
      (node (ref "C29") (pin "1") (pinfunction "1_1") (pintype "passive"))
      (node (ref "C3") (pin "1") (pinfunction "1_1") (pintype "passive"))
      (node (ref "C30") (pin "1") (pinfunction "1_1") (pintype "passive"))
      (node (ref "C31") (pin "2") (pinfunction "2_2") (pintype "passive"))
      (node (ref "C32") (pin "2") (pinfunction "2_2") (pintype "passive"))
      (node (ref "C33") (pin "2") (pinfunction "2_2") (pintype "passive"))
      (node (ref "C34") (pin "2") (pinfunction "2_2") (pintype "passive"))
      (node (ref "C35") (pin "2") (pinfunction "2_2") (pintype "passive"))
      (node (ref "C36") (pin "2") (pinfunction "2_2") (pintype "passive"))
      (node (ref "C37") (pin "2") (pinfunction "2_2") (pintype "passive"))
      (node (ref "C38") (pin "2") (pinfunction "2_2") (pintype "passive"))
      (node (ref "C39") (pin "2") (pinfunction "2_2") (pintype "passive"))
      (node (ref "C4") (pin "1") (pinfunction "1_1") (pintype "passive"))
      (node (ref "C40") (pin "2") (pinfunction "2_2") (pintype "passive"))
      (node (ref "C5") (pin "1") (pinfunction "1_1") (pintype "passive"))
      (node (ref "C6") (pin "1") (pinfunction "1_1") (pintype "passive"))
      (node (ref "C7") (pin "1") (pinfunction "1_1") (pintype "passive"))
      (node (ref "C8") (pin "1") (pinfunction "1_1") (pintype "passive"))
      (node (ref "C9") (pin "1") (pinfunction "1_1") (pintype "passive"))
      (node (ref "J1") (pin "5") (pintype "passive"))
      (node (ref "J1") (pin "6") (pintype "passive"))
      (node (ref "J2") (pin "5") (pintype "passive"))
      (node (ref "J2") (pin "6") (pintype "passive"))
      (node (ref "U1") (pin "4") (pinfunction "VCC_4") (pintype "power_in"))
      (node (ref "U10") (pin "4") (pinfunction "VCC_4") (pintype "power_in"))
      (node (ref "U11") (pin "4") (pinfunction "VCC_4") (pintype "power_in"))
      (node (ref "U12") (pin "4") (pinfunction "VCC_4") (pintype "power_in"))
      (node (ref "U13") (pin "4") (pinfunction "VCC_4") (pintype "power_in"))
      (node (ref "U14") (pin "4") (pinfunction "VCC_4") (pintype "power_in"))
      (node (ref "U15") (pin "4") (pinfunction "VCC_4") (pintype "power_in"))
      (node (ref "U16") (pin "4") (pinfunction "VCC_4") (pintype "power_in"))
      (node (ref "U17") (pin "4") (pinfunction "VCC_4") (pintype "power_in"))
      (node (ref "U18") (pin "4") (pinfunction "VCC_4") (pintype "power_in"))
      (node (ref "U19") (pin "4") (pinfunction "VCC_4") (pintype "power_in"))
      (node (ref "U2") (pin "4") (pinfunction "VCC_4") (pintype "power_in"))
      (node (ref "U20") (pin "4") (pinfunction "VCC_4") (pintype "power_in"))
      (node (ref "U21") (pin "4") (pinfunction "VCC_4") (pintype "power_in"))
      (node (ref "U22") (pin "4") (pinfunction "VCC_4") (pintype "power_in"))
      (node (ref "U23") (pin "4") (pinfunction "VCC_4") (pintype "power_in"))
      (node (ref "U24") (pin "4") (pinfunction "VCC_4") (pintype "power_in"))
      (node (ref "U25") (pin "4") (pinfunction "VCC_4") (pintype "power_in"))
      (node (ref "U26") (pin "4") (pinfunction "VCC_4") (pintype "power_in"))
      (node (ref "U27") (pin "4") (pinfunction "VCC_4") (pintype "power_in"))
      (node (ref "U28") (pin "4") (pinfunction "VCC_4") (pintype "power_in"))
      (node (ref "U29") (pin "4") (pinfunction "VCC_4") (pintype "power_in"))
      (node (ref "U3") (pin "4") (pinfunction "VCC_4") (pintype "power_in"))
      (node (ref "U30") (pin "4") (pinfunction "VCC_4") (pintype "power_in"))
      (node (ref "U4") (pin "4") (pinfunction "VCC_4") (pintype "power_in"))
      (node (ref "U5") (pin "4") (pinfunction "VCC_4") (pintype "power_in"))
      (node (ref "U6") (pin "4") (pinfunction "VCC_4") (pintype "power_in"))
      (node (ref "U7") (pin "4") (pinfunction "VCC_4") (pintype "power_in"))
      (node (ref "U8") (pin "4") (pinfunction "VCC_4") (pintype "power_in"))
      (node (ref "U9") (pin "4") (pinfunction "VCC_4") (pintype "power_in"))
    )
    (net (code "11") (name "/VCCBAT") (class "Default")
      (node (ref "D1") (pin "4") (pinfunction "+_4") (pintype "power_in"))
      (node (ref "D1") (pin "5") (pinfunction "+_5") (pintype "power_in"))
      (node (ref "D1") (pin "6") (pinfunction "+_6") (pintype "power_in"))
      (node (ref "D10") (pin "4") (pinfunction "+_4") (pintype "power_in"))
      (node (ref "D10") (pin "5") (pinfunction "+_5") (pintype "power_in"))
      (node (ref "D10") (pin "6") (pinfunction "+_6") (pintype "power_in"))
      (node (ref "D11") (pin "4") (pinfunction "+_4") (pintype "power_in"))
      (node (ref "D11") (pin "5") (pinfunction "+_5") (pintype "power_in"))
      (node (ref "D11") (pin "6") (pinfunction "+_6") (pintype "power_in"))
      (node (ref "D12") (pin "4") (pinfunction "+_4") (pintype "power_in"))
      (node (ref "D12") (pin "5") (pinfunction "+_5") (pintype "power_in"))
      (node (ref "D12") (pin "6") (pinfunction "+_6") (pintype "power_in"))
      (node (ref "D13") (pin "4") (pinfunction "+_4") (pintype "power_in"))
      (node (ref "D13") (pin "5") (pinfunction "+_5") (pintype "power_in"))
      (node (ref "D13") (pin "6") (pinfunction "+_6") (pintype "power_in"))
      (node (ref "D14") (pin "4") (pinfunction "+_4") (pintype "power_in"))
      (node (ref "D14") (pin "5") (pinfunction "+_5") (pintype "power_in"))
      (node (ref "D14") (pin "6") (pinfunction "+_6") (pintype "power_in"))
      (node (ref "D15") (pin "4") (pinfunction "+_4") (pintype "power_in"))
      (node (ref "D15") (pin "5") (pinfunction "+_5") (pintype "power_in"))
      (node (ref "D15") (pin "6") (pinfunction "+_6") (pintype "power_in"))
      (node (ref "D16") (pin "4") (pinfunction "+_4") (pintype "power_in"))
      (node (ref "D16") (pin "5") (pinfunction "+_5") (pintype "power_in"))
      (node (ref "D16") (pin "6") (pinfunction "+_6") (pintype "power_in"))
      (node (ref "D17") (pin "4") (pinfunction "+_4") (pintype "power_in"))
      (node (ref "D17") (pin "5") (pinfunction "+_5") (pintype "power_in"))
      (node (ref "D17") (pin "6") (pinfunction "+_6") (pintype "power_in"))
      (node (ref "D18") (pin "4") (pinfunction "+_4") (pintype "power_in"))
      (node (ref "D18") (pin "5") (pinfunction "+_5") (pintype "power_in"))
      (node (ref "D18") (pin "6") (pinfunction "+_6") (pintype "power_in"))
      (node (ref "D19") (pin "4") (pinfunction "+_4") (pintype "power_in"))
      (node (ref "D19") (pin "5") (pinfunction "+_5") (pintype "power_in"))
      (node (ref "D19") (pin "6") (pinfunction "+_6") (pintype "power_in"))
      (node (ref "D2") (pin "4") (pinfunction "+_4") (pintype "power_in"))
      (node (ref "D2") (pin "5") (pinfunction "+_5") (pintype "power_in"))
      (node (ref "D2") (pin "6") (pinfunction "+_6") (pintype "power_in"))
      (node (ref "D20") (pin "4") (pinfunction "+_4") (pintype "power_in"))
      (node (ref "D20") (pin "5") (pinfunction "+_5") (pintype "power_in"))
      (node (ref "D20") (pin "6") (pinfunction "+_6") (pintype "power_in"))
      (node (ref "D21") (pin "4") (pinfunction "+_4") (pintype "power_in"))
      (node (ref "D21") (pin "5") (pinfunction "+_5") (pintype "power_in"))
      (node (ref "D21") (pin "6") (pinfunction "+_6") (pintype "power_in"))
      (node (ref "D22") (pin "4") (pinfunction "+_4") (pintype "power_in"))
      (node (ref "D22") (pin "5") (pinfunction "+_5") (pintype "power_in"))
      (node (ref "D22") (pin "6") (pinfunction "+_6") (pintype "power_in"))
      (node (ref "D23") (pin "4") (pinfunction "+_4") (pintype "power_in"))
      (node (ref "D23") (pin "5") (pinfunction "+_5") (pintype "power_in"))
      (node (ref "D23") (pin "6") (pinfunction "+_6") (pintype "power_in"))
      (node (ref "D24") (pin "4") (pinfunction "+_4") (pintype "power_in"))
      (node (ref "D24") (pin "5") (pinfunction "+_5") (pintype "power_in"))
      (node (ref "D24") (pin "6") (pinfunction "+_6") (pintype "power_in"))
      (node (ref "D25") (pin "4") (pinfunction "+_4") (pintype "power_in"))
      (node (ref "D25") (pin "5") (pinfunction "+_5") (pintype "power_in"))
      (node (ref "D25") (pin "6") (pinfunction "+_6") (pintype "power_in"))
      (node (ref "D26") (pin "4") (pinfunction "+_4") (pintype "power_in"))
      (node (ref "D26") (pin "5") (pinfunction "+_5") (pintype "power_in"))
      (node (ref "D26") (pin "6") (pinfunction "+_6") (pintype "power_in"))
      (node (ref "D27") (pin "4") (pinfunction "+_4") (pintype "power_in"))
      (node (ref "D27") (pin "5") (pinfunction "+_5") (pintype "power_in"))
      (node (ref "D27") (pin "6") (pinfunction "+_6") (pintype "power_in"))
      (node (ref "D28") (pin "4") (pinfunction "+_4") (pintype "power_in"))
      (node (ref "D28") (pin "5") (pinfunction "+_5") (pintype "power_in"))
      (node (ref "D28") (pin "6") (pinfunction "+_6") (pintype "power_in"))
      (node (ref "D29") (pin "4") (pinfunction "+_4") (pintype "power_in"))
      (node (ref "D29") (pin "5") (pinfunction "+_5") (pintype "power_in"))
      (node (ref "D29") (pin "6") (pinfunction "+_6") (pintype "power_in"))
      (node (ref "D3") (pin "4") (pinfunction "+_4") (pintype "power_in"))
      (node (ref "D3") (pin "5") (pinfunction "+_5") (pintype "power_in"))
      (node (ref "D3") (pin "6") (pinfunction "+_6") (pintype "power_in"))
      (node (ref "D30") (pin "4") (pinfunction "+_4") (pintype "power_in"))
      (node (ref "D30") (pin "5") (pinfunction "+_5") (pintype "power_in"))
      (node (ref "D30") (pin "6") (pinfunction "+_6") (pintype "power_in"))
      (node (ref "D31") (pin "4") (pinfunction "+_4") (pintype "power_in"))
      (node (ref "D31") (pin "5") (pinfunction "+_5") (pintype "power_in"))
      (node (ref "D31") (pin "6") (pinfunction "+_6") (pintype "power_in"))
      (node (ref "D32") (pin "4") (pinfunction "+_4") (pintype "power_in"))
      (node (ref "D32") (pin "5") (pinfunction "+_5") (pintype "power_in"))
      (node (ref "D32") (pin "6") (pinfunction "+_6") (pintype "power_in"))
      (node (ref "D33") (pin "4") (pinfunction "+_4") (pintype "power_in"))
      (node (ref "D33") (pin "5") (pinfunction "+_5") (pintype "power_in"))
      (node (ref "D33") (pin "6") (pinfunction "+_6") (pintype "power_in"))
      (node (ref "D34") (pin "4") (pinfunction "+_4") (pintype "power_in"))
      (node (ref "D34") (pin "5") (pinfunction "+_5") (pintype "power_in"))
      (node (ref "D34") (pin "6") (pinfunction "+_6") (pintype "power_in"))
      (node (ref "D35") (pin "4") (pinfunction "+_4") (pintype "power_in"))
      (node (ref "D35") (pin "5") (pinfunction "+_5") (pintype "power_in"))
      (node (ref "D35") (pin "6") (pinfunction "+_6") (pintype "power_in"))
      (node (ref "D36") (pin "4") (pinfunction "+_4") (pintype "power_in"))
      (node (ref "D36") (pin "5") (pinfunction "+_5") (pintype "power_in"))
      (node (ref "D36") (pin "6") (pinfunction "+_6") (pintype "power_in"))
      (node (ref "D37") (pin "4") (pinfunction "+_4") (pintype "power_in"))
      (node (ref "D37") (pin "5") (pinfunction "+_5") (pintype "power_in"))
      (node (ref "D37") (pin "6") (pinfunction "+_6") (pintype "power_in"))
      (node (ref "D38") (pin "4") (pinfunction "+_4") (pintype "power_in"))
      (node (ref "D38") (pin "5") (pinfunction "+_5") (pintype "power_in"))
      (node (ref "D38") (pin "6") (pinfunction "+_6") (pintype "power_in"))
      (node (ref "D39") (pin "4") (pinfunction "+_4") (pintype "power_in"))
      (node (ref "D39") (pin "5") (pinfunction "+_5") (pintype "power_in"))
      (node (ref "D39") (pin "6") (pinfunction "+_6") (pintype "power_in"))
      (node (ref "D4") (pin "4") (pinfunction "+_4") (pintype "power_in"))
      (node (ref "D4") (pin "5") (pinfunction "+_5") (pintype "power_in"))
      (node (ref "D4") (pin "6") (pinfunction "+_6") (pintype "power_in"))
      (node (ref "D40") (pin "4") (pinfunction "+_4") (pintype "power_in"))
      (node (ref "D40") (pin "5") (pinfunction "+_5") (pintype "power_in"))
      (node (ref "D40") (pin "6") (pinfunction "+_6") (pintype "power_in"))
      (node (ref "D41") (pin "4") (pinfunction "+_4") (pintype "power_in"))
      (node (ref "D41") (pin "5") (pinfunction "+_5") (pintype "power_in"))
      (node (ref "D41") (pin "6") (pinfunction "+_6") (pintype "power_in"))
      (node (ref "D42") (pin "4") (pinfunction "+_4") (pintype "power_in"))
      (node (ref "D42") (pin "5") (pinfunction "+_5") (pintype "power_in"))
      (node (ref "D42") (pin "6") (pinfunction "+_6") (pintype "power_in"))
      (node (ref "D43") (pin "4") (pinfunction "+_4") (pintype "power_in"))
      (node (ref "D43") (pin "5") (pinfunction "+_5") (pintype "power_in"))
      (node (ref "D43") (pin "6") (pinfunction "+_6") (pintype "power_in"))
      (node (ref "D44") (pin "4") (pinfunction "+_4") (pintype "power_in"))
      (node (ref "D44") (pin "5") (pinfunction "+_5") (pintype "power_in"))
      (node (ref "D44") (pin "6") (pinfunction "+_6") (pintype "power_in"))
      (node (ref "D45") (pin "4") (pinfunction "+_4") (pintype "power_in"))
      (node (ref "D45") (pin "5") (pinfunction "+_5") (pintype "power_in"))
      (node (ref "D45") (pin "6") (pinfunction "+_6") (pintype "power_in"))
      (node (ref "D46") (pin "4") (pinfunction "+_4") (pintype "power_in"))
      (node (ref "D46") (pin "5") (pinfunction "+_5") (pintype "power_in"))
      (node (ref "D46") (pin "6") (pinfunction "+_6") (pintype "power_in"))
      (node (ref "D47") (pin "4") (pinfunction "+_4") (pintype "power_in"))
      (node (ref "D47") (pin "5") (pinfunction "+_5") (pintype "power_in"))
      (node (ref "D47") (pin "6") (pinfunction "+_6") (pintype "power_in"))
      (node (ref "D48") (pin "4") (pinfunction "+_4") (pintype "power_in"))
      (node (ref "D48") (pin "5") (pinfunction "+_5") (pintype "power_in"))
      (node (ref "D48") (pin "6") (pinfunction "+_6") (pintype "power_in"))
      (node (ref "D49") (pin "4") (pinfunction "+_4") (pintype "power_in"))
      (node (ref "D49") (pin "5") (pinfunction "+_5") (pintype "power_in"))
      (node (ref "D49") (pin "6") (pinfunction "+_6") (pintype "power_in"))
      (node (ref "D5") (pin "4") (pinfunction "+_4") (pintype "power_in"))
      (node (ref "D5") (pin "5") (pinfunction "+_5") (pintype "power_in"))
      (node (ref "D5") (pin "6") (pinfunction "+_6") (pintype "power_in"))
      (node (ref "D50") (pin "4") (pinfunction "+_4") (pintype "power_in"))
      (node (ref "D50") (pin "5") (pinfunction "+_5") (pintype "power_in"))
      (node (ref "D50") (pin "6") (pinfunction "+_6") (pintype "power_in"))
      (node (ref "D51") (pin "4") (pinfunction "+_4") (pintype "power_in"))
      (node (ref "D51") (pin "5") (pinfunction "+_5") (pintype "power_in"))
      (node (ref "D51") (pin "6") (pinfunction "+_6") (pintype "power_in"))
      (node (ref "D52") (pin "4") (pinfunction "+_4") (pintype "power_in"))
      (node (ref "D52") (pin "5") (pinfunction "+_5") (pintype "power_in"))
      (node (ref "D52") (pin "6") (pinfunction "+_6") (pintype "power_in"))
      (node (ref "D53") (pin "4") (pinfunction "+_4") (pintype "power_in"))
      (node (ref "D53") (pin "5") (pinfunction "+_5") (pintype "power_in"))
      (node (ref "D53") (pin "6") (pinfunction "+_6") (pintype "power_in"))
      (node (ref "D54") (pin "4") (pinfunction "+_4") (pintype "power_in"))
      (node (ref "D54") (pin "5") (pinfunction "+_5") (pintype "power_in"))
      (node (ref "D54") (pin "6") (pinfunction "+_6") (pintype "power_in"))
      (node (ref "D55") (pin "4") (pinfunction "+_4") (pintype "power_in"))
      (node (ref "D55") (pin "5") (pinfunction "+_5") (pintype "power_in"))
      (node (ref "D55") (pin "6") (pinfunction "+_6") (pintype "power_in"))
      (node (ref "D56") (pin "4") (pinfunction "+_4") (pintype "power_in"))
      (node (ref "D56") (pin "5") (pinfunction "+_5") (pintype "power_in"))
      (node (ref "D56") (pin "6") (pinfunction "+_6") (pintype "power_in"))
      (node (ref "D57") (pin "4") (pinfunction "+_4") (pintype "power_in"))
      (node (ref "D57") (pin "5") (pinfunction "+_5") (pintype "power_in"))
      (node (ref "D57") (pin "6") (pinfunction "+_6") (pintype "power_in"))
      (node (ref "D58") (pin "4") (pinfunction "+_4") (pintype "power_in"))
      (node (ref "D58") (pin "5") (pinfunction "+_5") (pintype "power_in"))
      (node (ref "D58") (pin "6") (pinfunction "+_6") (pintype "power_in"))
      (node (ref "D59") (pin "4") (pinfunction "+_4") (pintype "power_in"))
      (node (ref "D59") (pin "5") (pinfunction "+_5") (pintype "power_in"))
      (node (ref "D59") (pin "6") (pinfunction "+_6") (pintype "power_in"))
      (node (ref "D6") (pin "4") (pinfunction "+_4") (pintype "power_in"))
      (node (ref "D6") (pin "5") (pinfunction "+_5") (pintype "power_in"))
      (node (ref "D6") (pin "6") (pinfunction "+_6") (pintype "power_in"))
      (node (ref "D60") (pin "4") (pinfunction "+_4") (pintype "power_in"))
      (node (ref "D60") (pin "5") (pinfunction "+_5") (pintype "power_in"))
      (node (ref "D60") (pin "6") (pinfunction "+_6") (pintype "power_in"))
      (node (ref "D7") (pin "4") (pinfunction "+_4") (pintype "power_in"))
      (node (ref "D7") (pin "5") (pinfunction "+_5") (pintype "power_in"))
      (node (ref "D7") (pin "6") (pinfunction "+_6") (pintype "power_in"))
      (node (ref "D8") (pin "4") (pinfunction "+_4") (pintype "power_in"))
      (node (ref "D8") (pin "5") (pinfunction "+_5") (pintype "power_in"))
      (node (ref "D8") (pin "6") (pinfunction "+_6") (pintype "power_in"))
      (node (ref "D9") (pin "4") (pinfunction "+_4") (pintype "power_in"))
      (node (ref "D9") (pin "5") (pinfunction "+_5") (pintype "power_in"))
      (node (ref "D9") (pin "6") (pinfunction "+_6") (pintype "power_in"))
      (node (ref "J1") (pin "10") (pintype "passive"))
      (node (ref "J1") (pin "9") (pintype "passive"))
      (node (ref "J2") (pin "10") (pintype "passive"))
      (node (ref "J2") (pin "9") (pintype "passive"))
    )
    (net (code "12") (name "Net-(U1-OUT1)") (class "Default")
      (node (ref "D1") (pin "3") (pinfunction "-_3") (pintype "power_in"))
      (node (ref "U1") (pin "1") (pinfunction "OUT1_1") (pintype "output"))
    )
    (net (code "13") (name "Net-(U1-OUT2)") (class "Default")
      (node (ref "D1") (pin "2") (pinfunction "-_2") (pintype "power_in"))
      (node (ref "U1") (pin "2") (pinfunction "OUT2_2") (pintype "output"))
    )
    (net (code "14") (name "Net-(U1-OUT3)") (class "Default")
      (node (ref "D1") (pin "1") (pinfunction "-_1") (pintype "power_in"))
      (node (ref "U1") (pin "3") (pinfunction "OUT3_3") (pintype "output"))
    )
    (net (code "15") (name "Net-(U1-OUT4)") (class "Default")
      (node (ref "D2") (pin "3") (pinfunction "-_3") (pintype "power_in"))
      (node (ref "U1") (pin "6") (pinfunction "OUT4_6") (pintype "power_in"))
    )
    (net (code "16") (name "Net-(U1-OUT5)") (class "Default")
      (node (ref "D2") (pin "2") (pinfunction "-_2") (pintype "power_in"))
      (node (ref "U1") (pin "7") (pinfunction "OUT5_7") (pintype "output"))
    )
    (net (code "17") (name "Net-(U1-OUT6)") (class "Default")
      (node (ref "D2") (pin "1") (pinfunction "-_1") (pintype "power_in"))
      (node (ref "U1") (pin "8") (pinfunction "OUT6_8") (pintype "output"))
    )
    (net (code "18") (name "Net-(U1-SCLK)") (class "Default")
      (node (ref "U1") (pin "9") (pinfunction "SCLK_9") (pintype "bidirectional"))
      (node (ref "U2") (pin "16") (pinfunction "SCLKI_16") (pintype "bidirectional"))
    )
    (net (code "19") (name "Net-(U1-SD0)") (class "Default")
      (node (ref "U1") (pin "10") (pinfunction "SD0_10") (pintype "bidirectional"))
      (node (ref "U2") (pin "15") (pinfunction "SDI_15") (pintype "bidirectional"))
    )
    (net (code "20") (name "Net-(U2-OUT1)") (class "Default")
      (node (ref "D3") (pin "3") (pinfunction "-_3") (pintype "power_in"))
      (node (ref "U2") (pin "1") (pinfunction "OUT1_1") (pintype "output"))
    )
    (net (code "21") (name "Net-(U2-OUT2)") (class "Default")
      (node (ref "D3") (pin "2") (pinfunction "-_2") (pintype "power_in"))
      (node (ref "U2") (pin "2") (pinfunction "OUT2_2") (pintype "output"))
    )
    (net (code "22") (name "Net-(U2-OUT3)") (class "Default")
      (node (ref "D3") (pin "1") (pinfunction "-_1") (pintype "power_in"))
      (node (ref "U2") (pin "3") (pinfunction "OUT3_3") (pintype "output"))
    )
    (net (code "23") (name "Net-(U2-OUT4)") (class "Default")
      (node (ref "D4") (pin "3") (pinfunction "-_3") (pintype "power_in"))
      (node (ref "U2") (pin "6") (pinfunction "OUT4_6") (pintype "power_in"))
    )
    (net (code "24") (name "Net-(U2-OUT5)") (class "Default")
      (node (ref "D4") (pin "2") (pinfunction "-_2") (pintype "power_in"))
      (node (ref "U2") (pin "7") (pinfunction "OUT5_7") (pintype "output"))
    )
    (net (code "25") (name "Net-(U2-OUT6)") (class "Default")
      (node (ref "D4") (pin "1") (pinfunction "-_1") (pintype "power_in"))
      (node (ref "U2") (pin "8") (pinfunction "OUT6_8") (pintype "output"))
    )
    (net (code "26") (name "Net-(U2-SCLK)") (class "Default")
      (node (ref "U2") (pin "9") (pinfunction "SCLK_9") (pintype "bidirectional"))
      (node (ref "U3") (pin "16") (pinfunction "SCLKI_16") (pintype "bidirectional"))
    )
    (net (code "27") (name "Net-(U2-SD0)") (class "Default")
      (node (ref "U2") (pin "10") (pinfunction "SD0_10") (pintype "bidirectional"))
      (node (ref "U3") (pin "15") (pinfunction "SDI_15") (pintype "bidirectional"))
    )
    (net (code "28") (name "Net-(U3-OUT1)") (class "Default")
      (node (ref "D5") (pin "3") (pinfunction "-_3") (pintype "power_in"))
      (node (ref "U3") (pin "1") (pinfunction "OUT1_1") (pintype "output"))
    )
    (net (code "29") (name "Net-(U3-OUT2)") (class "Default")
      (node (ref "D5") (pin "2") (pinfunction "-_2") (pintype "power_in"))
      (node (ref "U3") (pin "2") (pinfunction "OUT2_2") (pintype "output"))
    )
    (net (code "30") (name "Net-(U3-OUT3)") (class "Default")
      (node (ref "D5") (pin "1") (pinfunction "-_1") (pintype "power_in"))
      (node (ref "U3") (pin "3") (pinfunction "OUT3_3") (pintype "output"))
    )
    (net (code "31") (name "Net-(U3-OUT4)") (class "Default")
      (node (ref "D6") (pin "3") (pinfunction "-_3") (pintype "power_in"))
      (node (ref "U3") (pin "6") (pinfunction "OUT4_6") (pintype "power_in"))
    )
    (net (code "32") (name "Net-(U3-OUT5)") (class "Default")
      (node (ref "D6") (pin "2") (pinfunction "-_2") (pintype "power_in"))
      (node (ref "U3") (pin "7") (pinfunction "OUT5_7") (pintype "output"))
    )
    (net (code "33") (name "Net-(U3-OUT6)") (class "Default")
      (node (ref "D6") (pin "1") (pinfunction "-_1") (pintype "power_in"))
      (node (ref "U3") (pin "8") (pinfunction "OUT6_8") (pintype "output"))
    )
    (net (code "34") (name "Net-(U3-SCLK)") (class "Default")
      (node (ref "U3") (pin "9") (pinfunction "SCLK_9") (pintype "bidirectional"))
      (node (ref "U4") (pin "16") (pinfunction "SCLKI_16") (pintype "bidirectional"))
    )
    (net (code "35") (name "Net-(U3-SD0)") (class "Default")
      (node (ref "U3") (pin "10") (pinfunction "SD0_10") (pintype "bidirectional"))
      (node (ref "U4") (pin "15") (pinfunction "SDI_15") (pintype "bidirectional"))
    )
    (net (code "36") (name "Net-(U4-OUT1)") (class "Default")
      (node (ref "D7") (pin "3") (pinfunction "-_3") (pintype "power_in"))
      (node (ref "U4") (pin "1") (pinfunction "OUT1_1") (pintype "output"))
    )
    (net (code "37") (name "Net-(U4-OUT2)") (class "Default")
      (node (ref "D7") (pin "2") (pinfunction "-_2") (pintype "power_in"))
      (node (ref "U4") (pin "2") (pinfunction "OUT2_2") (pintype "output"))
    )
    (net (code "38") (name "Net-(U4-OUT3)") (class "Default")
      (node (ref "D7") (pin "1") (pinfunction "-_1") (pintype "power_in"))
      (node (ref "U4") (pin "3") (pinfunction "OUT3_3") (pintype "output"))
    )
    (net (code "39") (name "Net-(U4-OUT4)") (class "Default")
      (node (ref "D8") (pin "3") (pinfunction "-_3") (pintype "power_in"))
      (node (ref "U4") (pin "6") (pinfunction "OUT4_6") (pintype "power_in"))
    )
    (net (code "40") (name "Net-(U4-OUT5)") (class "Default")
      (node (ref "D8") (pin "2") (pinfunction "-_2") (pintype "power_in"))
      (node (ref "U4") (pin "7") (pinfunction "OUT5_7") (pintype "output"))
    )
    (net (code "41") (name "Net-(U4-OUT6)") (class "Default")
      (node (ref "D8") (pin "1") (pinfunction "-_1") (pintype "power_in"))
      (node (ref "U4") (pin "8") (pinfunction "OUT6_8") (pintype "output"))
    )
    (net (code "42") (name "Net-(U4-SCLK)") (class "Default")
      (node (ref "U4") (pin "9") (pinfunction "SCLK_9") (pintype "bidirectional"))
      (node (ref "U5") (pin "16") (pinfunction "SCLKI_16") (pintype "bidirectional"))
    )
    (net (code "43") (name "Net-(U4-SD0)") (class "Default")
      (node (ref "U4") (pin "10") (pinfunction "SD0_10") (pintype "bidirectional"))
      (node (ref "U5") (pin "15") (pinfunction "SDI_15") (pintype "bidirectional"))
    )
    (net (code "44") (name "Net-(U5-OUT1)") (class "Default")
      (node (ref "D9") (pin "3") (pinfunction "-_3") (pintype "power_in"))
      (node (ref "U5") (pin "1") (pinfunction "OUT1_1") (pintype "output"))
    )
    (net (code "45") (name "Net-(U5-OUT2)") (class "Default")
      (node (ref "D9") (pin "2") (pinfunction "-_2") (pintype "power_in"))
      (node (ref "U5") (pin "2") (pinfunction "OUT2_2") (pintype "output"))
    )
    (net (code "46") (name "Net-(U5-OUT3)") (class "Default")
      (node (ref "D9") (pin "1") (pinfunction "-_1") (pintype "power_in"))
      (node (ref "U5") (pin "3") (pinfunction "OUT3_3") (pintype "output"))
    )
    (net (code "47") (name "Net-(U5-OUT4)") (class "Default")
      (node (ref "D10") (pin "3") (pinfunction "-_3") (pintype "power_in"))
      (node (ref "U5") (pin "6") (pinfunction "OUT4_6") (pintype "power_in"))
    )
    (net (code "48") (name "Net-(U5-OUT5)") (class "Default")
      (node (ref "D10") (pin "2") (pinfunction "-_2") (pintype "power_in"))
      (node (ref "U5") (pin "7") (pinfunction "OUT5_7") (pintype "output"))
    )
    (net (code "49") (name "Net-(U5-OUT6)") (class "Default")
      (node (ref "D10") (pin "1") (pinfunction "-_1") (pintype "power_in"))
      (node (ref "U5") (pin "8") (pinfunction "OUT6_8") (pintype "output"))
    )
    (net (code "50") (name "Net-(U5-SCLK)") (class "Default")
      (node (ref "U5") (pin "9") (pinfunction "SCLK_9") (pintype "bidirectional"))
      (node (ref "U6") (pin "16") (pinfunction "SCLKI_16") (pintype "bidirectional"))
    )
    (net (code "51") (name "Net-(U5-SD0)") (class "Default")
      (node (ref "U5") (pin "10") (pinfunction "SD0_10") (pintype "bidirectional"))
      (node (ref "U6") (pin "15") (pinfunction "SDI_15") (pintype "bidirectional"))
    )
    (net (code "52") (name "Net-(U6-OUT1)") (class "Default")
      (node (ref "D11") (pin "3") (pinfunction "-_3") (pintype "power_in"))
      (node (ref "U6") (pin "1") (pinfunction "OUT1_1") (pintype "output"))
    )
    (net (code "53") (name "Net-(U6-OUT2)") (class "Default")
      (node (ref "D11") (pin "2") (pinfunction "-_2") (pintype "power_in"))
      (node (ref "U6") (pin "2") (pinfunction "OUT2_2") (pintype "output"))
    )
    (net (code "54") (name "Net-(U6-OUT3)") (class "Default")
      (node (ref "D11") (pin "1") (pinfunction "-_1") (pintype "power_in"))
      (node (ref "U6") (pin "3") (pinfunction "OUT3_3") (pintype "output"))
    )
    (net (code "55") (name "Net-(U6-OUT4)") (class "Default")
      (node (ref "D12") (pin "3") (pinfunction "-_3") (pintype "power_in"))
      (node (ref "U6") (pin "6") (pinfunction "OUT4_6") (pintype "power_in"))
    )
    (net (code "56") (name "Net-(U6-OUT5)") (class "Default")
      (node (ref "D12") (pin "2") (pinfunction "-_2") (pintype "power_in"))
      (node (ref "U6") (pin "7") (pinfunction "OUT5_7") (pintype "output"))
    )
    (net (code "57") (name "Net-(U6-OUT6)") (class "Default")
      (node (ref "D12") (pin "1") (pinfunction "-_1") (pintype "power_in"))
      (node (ref "U6") (pin "8") (pinfunction "OUT6_8") (pintype "output"))
    )
    (net (code "58") (name "Net-(U6-SCLK)") (class "Default")
      (node (ref "U6") (pin "9") (pinfunction "SCLK_9") (pintype "bidirectional"))
      (node (ref "U7") (pin "16") (pinfunction "SCLKI_16") (pintype "bidirectional"))
    )
    (net (code "59") (name "Net-(U6-SD0)") (class "Default")
      (node (ref "U6") (pin "10") (pinfunction "SD0_10") (pintype "bidirectional"))
      (node (ref "U7") (pin "15") (pinfunction "SDI_15") (pintype "bidirectional"))
    )
    (net (code "60") (name "Net-(U7-OUT1)") (class "Default")
      (node (ref "D13") (pin "3") (pinfunction "-_3") (pintype "power_in"))
      (node (ref "U7") (pin "1") (pinfunction "OUT1_1") (pintype "output"))
    )
    (net (code "61") (name "Net-(U7-OUT2)") (class "Default")
      (node (ref "D13") (pin "2") (pinfunction "-_2") (pintype "power_in"))
      (node (ref "U7") (pin "2") (pinfunction "OUT2_2") (pintype "output"))
    )
    (net (code "62") (name "Net-(U7-OUT3)") (class "Default")
      (node (ref "D13") (pin "1") (pinfunction "-_1") (pintype "power_in"))
      (node (ref "U7") (pin "3") (pinfunction "OUT3_3") (pintype "output"))
    )
    (net (code "63") (name "Net-(U7-OUT4)") (class "Default")
      (node (ref "D14") (pin "3") (pinfunction "-_3") (pintype "power_in"))
      (node (ref "U7") (pin "6") (pinfunction "OUT4_6") (pintype "power_in"))
    )
    (net (code "64") (name "Net-(U7-OUT5)") (class "Default")
      (node (ref "D14") (pin "2") (pinfunction "-_2") (pintype "power_in"))
      (node (ref "U7") (pin "7") (pinfunction "OUT5_7") (pintype "output"))
    )
    (net (code "65") (name "Net-(U7-OUT6)") (class "Default")
      (node (ref "D14") (pin "1") (pinfunction "-_1") (pintype "power_in"))
      (node (ref "U7") (pin "8") (pinfunction "OUT6_8") (pintype "output"))
    )
    (net (code "66") (name "Net-(U7-SCLK)") (class "Default")
      (node (ref "U7") (pin "9") (pinfunction "SCLK_9") (pintype "bidirectional"))
      (node (ref "U8") (pin "16") (pinfunction "SCLKI_16") (pintype "bidirectional"))
    )
    (net (code "67") (name "Net-(U7-SD0)") (class "Default")
      (node (ref "U7") (pin "10") (pinfunction "SD0_10") (pintype "bidirectional"))
      (node (ref "U8") (pin "15") (pinfunction "SDI_15") (pintype "bidirectional"))
    )
    (net (code "68") (name "Net-(U8-OUT1)") (class "Default")
      (node (ref "D15") (pin "3") (pinfunction "-_3") (pintype "power_in"))
      (node (ref "U8") (pin "1") (pinfunction "OUT1_1") (pintype "output"))
    )
    (net (code "69") (name "Net-(U8-OUT2)") (class "Default")
      (node (ref "D15") (pin "2") (pinfunction "-_2") (pintype "power_in"))
      (node (ref "U8") (pin "2") (pinfunction "OUT2_2") (pintype "output"))
    )
    (net (code "70") (name "Net-(U8-OUT3)") (class "Default")
      (node (ref "D15") (pin "1") (pinfunction "-_1") (pintype "power_in"))
      (node (ref "U8") (pin "3") (pinfunction "OUT3_3") (pintype "output"))
    )
    (net (code "71") (name "Net-(U8-OUT4)") (class "Default")
      (node (ref "D16") (pin "3") (pinfunction "-_3") (pintype "power_in"))
      (node (ref "U8") (pin "6") (pinfunction "OUT4_6") (pintype "power_in"))
    )
    (net (code "72") (name "Net-(U8-OUT5)") (class "Default")
      (node (ref "D16") (pin "2") (pinfunction "-_2") (pintype "power_in"))
      (node (ref "U8") (pin "7") (pinfunction "OUT5_7") (pintype "output"))
    )
    (net (code "73") (name "Net-(U8-OUT6)") (class "Default")
      (node (ref "D16") (pin "1") (pinfunction "-_1") (pintype "power_in"))
      (node (ref "U8") (pin "8") (pinfunction "OUT6_8") (pintype "output"))
    )
    (net (code "74") (name "Net-(U8-SCLK)") (class "Default")
      (node (ref "U8") (pin "9") (pinfunction "SCLK_9") (pintype "bidirectional"))
      (node (ref "U9") (pin "16") (pinfunction "SCLKI_16") (pintype "bidirectional"))
    )
    (net (code "75") (name "Net-(U8-SD0)") (class "Default")
      (node (ref "U8") (pin "10") (pinfunction "SD0_10") (pintype "bidirectional"))
      (node (ref "U9") (pin "15") (pinfunction "SDI_15") (pintype "bidirectional"))
    )
    (net (code "76") (name "Net-(U9-OUT1)") (class "Default")
      (node (ref "D17") (pin "3") (pinfunction "-_3") (pintype "power_in"))
      (node (ref "U9") (pin "1") (pinfunction "OUT1_1") (pintype "output"))
    )
    (net (code "77") (name "Net-(U9-OUT2)") (class "Default")
      (node (ref "D17") (pin "2") (pinfunction "-_2") (pintype "power_in"))
      (node (ref "U9") (pin "2") (pinfunction "OUT2_2") (pintype "output"))
    )
    (net (code "78") (name "Net-(U9-OUT3)") (class "Default")
      (node (ref "D17") (pin "1") (pinfunction "-_1") (pintype "power_in"))
      (node (ref "U9") (pin "3") (pinfunction "OUT3_3") (pintype "output"))
    )
    (net (code "79") (name "Net-(U9-OUT4)") (class "Default")
      (node (ref "D18") (pin "3") (pinfunction "-_3") (pintype "power_in"))
      (node (ref "U9") (pin "6") (pinfunction "OUT4_6") (pintype "power_in"))
    )
    (net (code "80") (name "Net-(U9-OUT5)") (class "Default")
      (node (ref "D18") (pin "2") (pinfunction "-_2") (pintype "power_in"))
      (node (ref "U9") (pin "7") (pinfunction "OUT5_7") (pintype "output"))
    )
    (net (code "81") (name "Net-(U9-OUT6)") (class "Default")
      (node (ref "D18") (pin "1") (pinfunction "-_1") (pintype "power_in"))
      (node (ref "U9") (pin "8") (pinfunction "OUT6_8") (pintype "output"))
    )
    (net (code "82") (name "Net-(U10-OUT1)") (class "Default")
      (node (ref "D19") (pin "3") (pinfunction "-_3") (pintype "power_in"))
      (node (ref "U10") (pin "1") (pinfunction "OUT1_1") (pintype "output"))
    )
    (net (code "83") (name "Net-(U10-OUT2)") (class "Default")
      (node (ref "D19") (pin "2") (pinfunction "-_2") (pintype "power_in"))
      (node (ref "U10") (pin "2") (pinfunction "OUT2_2") (pintype "output"))
    )
    (net (code "84") (name "Net-(U10-OUT3)") (class "Default")
      (node (ref "D19") (pin "1") (pinfunction "-_1") (pintype "power_in"))
      (node (ref "U10") (pin "3") (pinfunction "OUT3_3") (pintype "output"))
    )
    (net (code "85") (name "Net-(U10-OUT4)") (class "Default")
      (node (ref "D20") (pin "3") (pinfunction "-_3") (pintype "power_in"))
      (node (ref "U10") (pin "6") (pinfunction "OUT4_6") (pintype "power_in"))
    )
    (net (code "86") (name "Net-(U10-OUT5)") (class "Default")
      (node (ref "D20") (pin "2") (pinfunction "-_2") (pintype "power_in"))
      (node (ref "U10") (pin "7") (pinfunction "OUT5_7") (pintype "output"))
    )
    (net (code "87") (name "Net-(U10-OUT6)") (class "Default")
      (node (ref "D20") (pin "1") (pinfunction "-_1") (pintype "power_in"))
      (node (ref "U10") (pin "8") (pinfunction "OUT6_8") (pintype "output"))
    )
    (net (code "88") (name "Net-(U10-SCLKI)") (class "Default")
      (node (ref "U10") (pin "16") (pinfunction "SCLKI_16") (pintype "bidirectional"))
      (node (ref "U9") (pin "9") (pinfunction "SCLK_9") (pintype "bidirectional"))
    )
    (net (code "89") (name "Net-(U10-SDI)") (class "Default")
      (node (ref "U10") (pin "15") (pinfunction "SDI_15") (pintype "bidirectional"))
      (node (ref "U9") (pin "10") (pinfunction "SD0_10") (pintype "bidirectional"))
    )
    (net (code "90") (name "Net-(U11-OUT1)") (class "Default")
      (node (ref "D21") (pin "3") (pinfunction "-_3") (pintype "power_in"))
      (node (ref "U11") (pin "1") (pinfunction "OUT1_1") (pintype "output"))
    )
    (net (code "91") (name "Net-(U11-OUT2)") (class "Default")
      (node (ref "D21") (pin "2") (pinfunction "-_2") (pintype "power_in"))
      (node (ref "U11") (pin "2") (pinfunction "OUT2_2") (pintype "output"))
    )
    (net (code "92") (name "Net-(U11-OUT3)") (class "Default")
      (node (ref "D21") (pin "1") (pinfunction "-_1") (pintype "power_in"))
      (node (ref "U11") (pin "3") (pinfunction "OUT3_3") (pintype "output"))
    )
    (net (code "93") (name "Net-(U11-OUT4)") (class "Default")
      (node (ref "D22") (pin "3") (pinfunction "-_3") (pintype "power_in"))
      (node (ref "U11") (pin "6") (pinfunction "OUT4_6") (pintype "power_in"))
    )
    (net (code "94") (name "Net-(U11-OUT5)") (class "Default")
      (node (ref "D22") (pin "2") (pinfunction "-_2") (pintype "power_in"))
      (node (ref "U11") (pin "7") (pinfunction "OUT5_7") (pintype "output"))
    )
    (net (code "95") (name "Net-(U11-OUT6)") (class "Default")
      (node (ref "D22") (pin "1") (pinfunction "-_1") (pintype "power_in"))
      (node (ref "U11") (pin "8") (pinfunction "OUT6_8") (pintype "output"))
    )
    (net (code "96") (name "Net-(U11-SCLK)") (class "Default")
      (node (ref "U11") (pin "9") (pinfunction "SCLK_9") (pintype "bidirectional"))
      (node (ref "U12") (pin "16") (pinfunction "SCLKI_16") (pintype "bidirectional"))
    )
    (net (code "97") (name "Net-(U11-SD0)") (class "Default")
      (node (ref "U11") (pin "10") (pinfunction "SD0_10") (pintype "bidirectional"))
      (node (ref "U12") (pin "15") (pinfunction "SDI_15") (pintype "bidirectional"))
    )
    (net (code "98") (name "Net-(U12-OUT1)") (class "Default")
      (node (ref "D23") (pin "3") (pinfunction "-_3") (pintype "power_in"))
      (node (ref "U12") (pin "1") (pinfunction "OUT1_1") (pintype "output"))
    )
    (net (code "99") (name "Net-(U12-OUT2)") (class "Default")
      (node (ref "D23") (pin "2") (pinfunction "-_2") (pintype "power_in"))
      (node (ref "U12") (pin "2") (pinfunction "OUT2_2") (pintype "output"))
    )
    (net (code "100") (name "Net-(U12-OUT3)") (class "Default")
      (node (ref "D23") (pin "1") (pinfunction "-_1") (pintype "power_in"))
      (node (ref "U12") (pin "3") (pinfunction "OUT3_3") (pintype "output"))
    )
    (net (code "101") (name "Net-(U12-OUT4)") (class "Default")
      (node (ref "D24") (pin "3") (pinfunction "-_3") (pintype "power_in"))
      (node (ref "U12") (pin "6") (pinfunction "OUT4_6") (pintype "power_in"))
    )
    (net (code "102") (name "Net-(U12-OUT5)") (class "Default")
      (node (ref "D24") (pin "2") (pinfunction "-_2") (pintype "power_in"))
      (node (ref "U12") (pin "7") (pinfunction "OUT5_7") (pintype "output"))
    )
    (net (code "103") (name "Net-(U12-OUT6)") (class "Default")
      (node (ref "D24") (pin "1") (pinfunction "-_1") (pintype "power_in"))
      (node (ref "U12") (pin "8") (pinfunction "OUT6_8") (pintype "output"))
    )
    (net (code "104") (name "Net-(U12-SCLK)") (class "Default")
      (node (ref "U12") (pin "9") (pinfunction "SCLK_9") (pintype "bidirectional"))
      (node (ref "U13") (pin "16") (pinfunction "SCLKI_16") (pintype "bidirectional"))
    )
    (net (code "105") (name "Net-(U12-SD0)") (class "Default")
      (node (ref "U12") (pin "10") (pinfunction "SD0_10") (pintype "bidirectional"))
      (node (ref "U13") (pin "15") (pinfunction "SDI_15") (pintype "bidirectional"))
    )
    (net (code "106") (name "Net-(U13-OUT1)") (class "Default")
      (node (ref "D25") (pin "3") (pinfunction "-_3") (pintype "power_in"))
      (node (ref "U13") (pin "1") (pinfunction "OUT1_1") (pintype "output"))
    )
    (net (code "107") (name "Net-(U13-OUT2)") (class "Default")
      (node (ref "D25") (pin "2") (pinfunction "-_2") (pintype "power_in"))
      (node (ref "U13") (pin "2") (pinfunction "OUT2_2") (pintype "output"))
    )
    (net (code "108") (name "Net-(U13-OUT3)") (class "Default")
      (node (ref "D25") (pin "1") (pinfunction "-_1") (pintype "power_in"))
      (node (ref "U13") (pin "3") (pinfunction "OUT3_3") (pintype "output"))
    )
    (net (code "109") (name "Net-(U13-OUT4)") (class "Default")
      (node (ref "D26") (pin "3") (pinfunction "-_3") (pintype "power_in"))
      (node (ref "U13") (pin "6") (pinfunction "OUT4_6") (pintype "power_in"))
    )
    (net (code "110") (name "Net-(U13-OUT5)") (class "Default")
      (node (ref "D26") (pin "2") (pinfunction "-_2") (pintype "power_in"))
      (node (ref "U13") (pin "7") (pinfunction "OUT5_7") (pintype "output"))
    )
    (net (code "111") (name "Net-(U13-OUT6)") (class "Default")
      (node (ref "D26") (pin "1") (pinfunction "-_1") (pintype "power_in"))
      (node (ref "U13") (pin "8") (pinfunction "OUT6_8") (pintype "output"))
    )
    (net (code "112") (name "Net-(U13-SCLK)") (class "Default")
      (node (ref "U13") (pin "9") (pinfunction "SCLK_9") (pintype "bidirectional"))
      (node (ref "U14") (pin "16") (pinfunction "SCLKI_16") (pintype "bidirectional"))
    )
    (net (code "113") (name "Net-(U13-SD0)") (class "Default")
      (node (ref "U13") (pin "10") (pinfunction "SD0_10") (pintype "bidirectional"))
      (node (ref "U14") (pin "15") (pinfunction "SDI_15") (pintype "bidirectional"))
    )
    (net (code "114") (name "Net-(U14-OUT1)") (class "Default")
      (node (ref "D27") (pin "3") (pinfunction "-_3") (pintype "power_in"))
      (node (ref "U14") (pin "1") (pinfunction "OUT1_1") (pintype "output"))
    )
    (net (code "115") (name "Net-(U14-OUT2)") (class "Default")
      (node (ref "D27") (pin "2") (pinfunction "-_2") (pintype "power_in"))
      (node (ref "U14") (pin "2") (pinfunction "OUT2_2") (pintype "output"))
    )
    (net (code "116") (name "Net-(U14-OUT3)") (class "Default")
      (node (ref "D27") (pin "1") (pinfunction "-_1") (pintype "power_in"))
      (node (ref "U14") (pin "3") (pinfunction "OUT3_3") (pintype "output"))
    )
    (net (code "117") (name "Net-(U14-OUT4)") (class "Default")
      (node (ref "D28") (pin "3") (pinfunction "-_3") (pintype "power_in"))
      (node (ref "U14") (pin "6") (pinfunction "OUT4_6") (pintype "power_in"))
    )
    (net (code "118") (name "Net-(U14-OUT5)") (class "Default")
      (node (ref "D28") (pin "2") (pinfunction "-_2") (pintype "power_in"))
      (node (ref "U14") (pin "7") (pinfunction "OUT5_7") (pintype "output"))
    )
    (net (code "119") (name "Net-(U14-OUT6)") (class "Default")
      (node (ref "D28") (pin "1") (pinfunction "-_1") (pintype "power_in"))
      (node (ref "U14") (pin "8") (pinfunction "OUT6_8") (pintype "output"))
    )
    (net (code "120") (name "Net-(U14-SCLK)") (class "Default")
      (node (ref "U14") (pin "9") (pinfunction "SCLK_9") (pintype "bidirectional"))
      (node (ref "U15") (pin "16") (pinfunction "SCLKI_16") (pintype "bidirectional"))
    )
    (net (code "121") (name "Net-(U14-SD0)") (class "Default")
      (node (ref "U14") (pin "10") (pinfunction "SD0_10") (pintype "bidirectional"))
      (node (ref "U15") (pin "15") (pinfunction "SDI_15") (pintype "bidirectional"))
    )
    (net (code "122") (name "Net-(U15-OUT1)") (class "Default")
      (node (ref "D29") (pin "3") (pinfunction "-_3") (pintype "power_in"))
      (node (ref "U15") (pin "1") (pinfunction "OUT1_1") (pintype "output"))
    )
    (net (code "123") (name "Net-(U15-OUT2)") (class "Default")
      (node (ref "D29") (pin "2") (pinfunction "-_2") (pintype "power_in"))
      (node (ref "U15") (pin "2") (pinfunction "OUT2_2") (pintype "output"))
    )
    (net (code "124") (name "Net-(U15-OUT3)") (class "Default")
      (node (ref "D29") (pin "1") (pinfunction "-_1") (pintype "power_in"))
      (node (ref "U15") (pin "3") (pinfunction "OUT3_3") (pintype "output"))
    )
    (net (code "125") (name "Net-(U15-OUT4)") (class "Default")
      (node (ref "D30") (pin "3") (pinfunction "-_3") (pintype "power_in"))
      (node (ref "U15") (pin "6") (pinfunction "OUT4_6") (pintype "power_in"))
    )
    (net (code "126") (name "Net-(U15-OUT5)") (class "Default")
      (node (ref "D30") (pin "2") (pinfunction "-_2") (pintype "power_in"))
      (node (ref "U15") (pin "7") (pinfunction "OUT5_7") (pintype "output"))
    )
    (net (code "127") (name "Net-(U15-OUT6)") (class "Default")
      (node (ref "D30") (pin "1") (pinfunction "-_1") (pintype "power_in"))
      (node (ref "U15") (pin "8") (pinfunction "OUT6_8") (pintype "output"))
    )
    (net (code "128") (name "Net-(U15-SCLK)") (class "Default")
      (node (ref "U15") (pin "9") (pinfunction "SCLK_9") (pintype "bidirectional"))
      (node (ref "U16") (pin "16") (pinfunction "SCLKI_16") (pintype "bidirectional"))
    )
    (net (code "129") (name "Net-(U15-SD0)") (class "Default")
      (node (ref "U15") (pin "10") (pinfunction "SD0_10") (pintype "bidirectional"))
      (node (ref "U16") (pin "15") (pinfunction "SDI_15") (pintype "bidirectional"))
    )
    (net (code "130") (name "Net-(U16-OUT1)") (class "Default")
      (node (ref "D31") (pin "3") (pinfunction "-_3") (pintype "power_in"))
      (node (ref "U16") (pin "1") (pinfunction "OUT1_1") (pintype "output"))
    )
    (net (code "131") (name "Net-(U16-OUT2)") (class "Default")
      (node (ref "D31") (pin "2") (pinfunction "-_2") (pintype "power_in"))
      (node (ref "U16") (pin "2") (pinfunction "OUT2_2") (pintype "output"))
    )
    (net (code "132") (name "Net-(U16-OUT3)") (class "Default")
      (node (ref "D31") (pin "1") (pinfunction "-_1") (pintype "power_in"))
      (node (ref "U16") (pin "3") (pinfunction "OUT3_3") (pintype "output"))
    )
    (net (code "133") (name "Net-(U16-OUT4)") (class "Default")
      (node (ref "D32") (pin "3") (pinfunction "-_3") (pintype "power_in"))
      (node (ref "U16") (pin "6") (pinfunction "OUT4_6") (pintype "power_in"))
    )
    (net (code "134") (name "Net-(U16-OUT5)") (class "Default")
      (node (ref "D32") (pin "2") (pinfunction "-_2") (pintype "power_in"))
      (node (ref "U16") (pin "7") (pinfunction "OUT5_7") (pintype "output"))
    )
    (net (code "135") (name "Net-(U16-OUT6)") (class "Default")
      (node (ref "D32") (pin "1") (pinfunction "-_1") (pintype "power_in"))
      (node (ref "U16") (pin "8") (pinfunction "OUT6_8") (pintype "output"))
    )
    (net (code "136") (name "Net-(U16-SCLK)") (class "Default")
      (node (ref "U16") (pin "9") (pinfunction "SCLK_9") (pintype "bidirectional"))
      (node (ref "U17") (pin "16") (pinfunction "SCLKI_16") (pintype "bidirectional"))
    )
    (net (code "137") (name "Net-(U16-SD0)") (class "Default")
      (node (ref "U16") (pin "10") (pinfunction "SD0_10") (pintype "bidirectional"))
      (node (ref "U17") (pin "15") (pinfunction "SDI_15") (pintype "bidirectional"))
    )
    (net (code "138") (name "Net-(U17-OUT1)") (class "Default")
      (node (ref "D33") (pin "3") (pinfunction "-_3") (pintype "power_in"))
      (node (ref "U17") (pin "1") (pinfunction "OUT1_1") (pintype "output"))
    )
    (net (code "139") (name "Net-(U17-OUT2)") (class "Default")
      (node (ref "D33") (pin "2") (pinfunction "-_2") (pintype "power_in"))
      (node (ref "U17") (pin "2") (pinfunction "OUT2_2") (pintype "output"))
    )
    (net (code "140") (name "Net-(U17-OUT3)") (class "Default")
      (node (ref "D33") (pin "1") (pinfunction "-_1") (pintype "power_in"))
      (node (ref "U17") (pin "3") (pinfunction "OUT3_3") (pintype "output"))
    )
    (net (code "141") (name "Net-(U17-OUT4)") (class "Default")
      (node (ref "D34") (pin "3") (pinfunction "-_3") (pintype "power_in"))
      (node (ref "U17") (pin "6") (pinfunction "OUT4_6") (pintype "power_in"))
    )
    (net (code "142") (name "Net-(U17-OUT5)") (class "Default")
      (node (ref "D34") (pin "2") (pinfunction "-_2") (pintype "power_in"))
      (node (ref "U17") (pin "7") (pinfunction "OUT5_7") (pintype "output"))
    )
    (net (code "143") (name "Net-(U17-OUT6)") (class "Default")
      (node (ref "D34") (pin "1") (pinfunction "-_1") (pintype "power_in"))
      (node (ref "U17") (pin "8") (pinfunction "OUT6_8") (pintype "output"))
    )
    (net (code "144") (name "Net-(U17-SCLK)") (class "Default")
      (node (ref "U17") (pin "9") (pinfunction "SCLK_9") (pintype "bidirectional"))
      (node (ref "U18") (pin "16") (pinfunction "SCLKI_16") (pintype "bidirectional"))
    )
    (net (code "145") (name "Net-(U17-SD0)") (class "Default")
      (node (ref "U17") (pin "10") (pinfunction "SD0_10") (pintype "bidirectional"))
      (node (ref "U18") (pin "15") (pinfunction "SDI_15") (pintype "bidirectional"))
    )
    (net (code "146") (name "Net-(U18-OUT1)") (class "Default")
      (node (ref "D35") (pin "3") (pinfunction "-_3") (pintype "power_in"))
      (node (ref "U18") (pin "1") (pinfunction "OUT1_1") (pintype "output"))
    )
    (net (code "147") (name "Net-(U18-OUT2)") (class "Default")
      (node (ref "D35") (pin "2") (pinfunction "-_2") (pintype "power_in"))
      (node (ref "U18") (pin "2") (pinfunction "OUT2_2") (pintype "output"))
    )
    (net (code "148") (name "Net-(U18-OUT3)") (class "Default")
      (node (ref "D35") (pin "1") (pinfunction "-_1") (pintype "power_in"))
      (node (ref "U18") (pin "3") (pinfunction "OUT3_3") (pintype "output"))
    )
    (net (code "149") (name "Net-(U18-OUT4)") (class "Default")
      (node (ref "D36") (pin "3") (pinfunction "-_3") (pintype "power_in"))
      (node (ref "U18") (pin "6") (pinfunction "OUT4_6") (pintype "power_in"))
    )
    (net (code "150") (name "Net-(U18-OUT5)") (class "Default")
      (node (ref "D36") (pin "2") (pinfunction "-_2") (pintype "power_in"))
      (node (ref "U18") (pin "7") (pinfunction "OUT5_7") (pintype "output"))
    )
    (net (code "151") (name "Net-(U18-OUT6)") (class "Default")
      (node (ref "D36") (pin "1") (pinfunction "-_1") (pintype "power_in"))
      (node (ref "U18") (pin "8") (pinfunction "OUT6_8") (pintype "output"))
    )
    (net (code "152") (name "Net-(U18-SCLK)") (class "Default")
      (node (ref "U18") (pin "9") (pinfunction "SCLK_9") (pintype "bidirectional"))
      (node (ref "U19") (pin "16") (pinfunction "SCLKI_16") (pintype "bidirectional"))
    )
    (net (code "153") (name "Net-(U18-SD0)") (class "Default")
      (node (ref "U18") (pin "10") (pinfunction "SD0_10") (pintype "bidirectional"))
      (node (ref "U19") (pin "15") (pinfunction "SDI_15") (pintype "bidirectional"))
    )
    (net (code "154") (name "Net-(U19-OUT1)") (class "Default")
      (node (ref "D37") (pin "3") (pinfunction "-_3") (pintype "power_in"))
      (node (ref "U19") (pin "1") (pinfunction "OUT1_1") (pintype "output"))
    )
    (net (code "155") (name "Net-(U19-OUT2)") (class "Default")
      (node (ref "D37") (pin "2") (pinfunction "-_2") (pintype "power_in"))
      (node (ref "U19") (pin "2") (pinfunction "OUT2_2") (pintype "output"))
    )
    (net (code "156") (name "Net-(U19-OUT3)") (class "Default")
      (node (ref "D37") (pin "1") (pinfunction "-_1") (pintype "power_in"))
      (node (ref "U19") (pin "3") (pinfunction "OUT3_3") (pintype "output"))
    )
    (net (code "157") (name "Net-(U19-OUT4)") (class "Default")
      (node (ref "D38") (pin "3") (pinfunction "-_3") (pintype "power_in"))
      (node (ref "U19") (pin "6") (pinfunction "OUT4_6") (pintype "power_in"))
    )
    (net (code "158") (name "Net-(U19-OUT5)") (class "Default")
      (node (ref "D38") (pin "2") (pinfunction "-_2") (pintype "power_in"))
      (node (ref "U19") (pin "7") (pinfunction "OUT5_7") (pintype "output"))
    )
    (net (code "159") (name "Net-(U19-OUT6)") (class "Default")
      (node (ref "D38") (pin "1") (pinfunction "-_1") (pintype "power_in"))
      (node (ref "U19") (pin "8") (pinfunction "OUT6_8") (pintype "output"))
    )
    (net (code "160") (name "Net-(U19-SCLK)") (class "Default")
      (node (ref "U19") (pin "9") (pinfunction "SCLK_9") (pintype "bidirectional"))
      (node (ref "U20") (pin "16") (pinfunction "SCLKI_16") (pintype "bidirectional"))
    )
    (net (code "161") (name "Net-(U19-SD0)") (class "Default")
      (node (ref "U19") (pin "10") (pinfunction "SD0_10") (pintype "bidirectional"))
      (node (ref "U20") (pin "15") (pinfunction "SDI_15") (pintype "bidirectional"))
    )
    (net (code "162") (name "Net-(U20-OUT1)") (class "Default")
      (node (ref "D39") (pin "3") (pinfunction "-_3") (pintype "power_in"))
      (node (ref "U20") (pin "1") (pinfunction "OUT1_1") (pintype "output"))
    )
    (net (code "163") (name "Net-(U20-OUT2)") (class "Default")
      (node (ref "D39") (pin "2") (pinfunction "-_2") (pintype "power_in"))
      (node (ref "U20") (pin "2") (pinfunction "OUT2_2") (pintype "output"))
    )
    (net (code "164") (name "Net-(U20-OUT3)") (class "Default")
      (node (ref "D39") (pin "1") (pinfunction "-_1") (pintype "power_in"))
      (node (ref "U20") (pin "3") (pinfunction "OUT3_3") (pintype "output"))
    )
    (net (code "165") (name "Net-(U20-OUT4)") (class "Default")
      (node (ref "D40") (pin "3") (pinfunction "-_3") (pintype "power_in"))
      (node (ref "U20") (pin "6") (pinfunction "OUT4_6") (pintype "power_in"))
    )
    (net (code "166") (name "Net-(U20-OUT5)") (class "Default")
      (node (ref "D40") (pin "2") (pinfunction "-_2") (pintype "power_in"))
      (node (ref "U20") (pin "7") (pinfunction "OUT5_7") (pintype "output"))
    )
    (net (code "167") (name "Net-(U20-OUT6)") (class "Default")
      (node (ref "D40") (pin "1") (pinfunction "-_1") (pintype "power_in"))
      (node (ref "U20") (pin "8") (pinfunction "OUT6_8") (pintype "output"))
    )
    (net (code "168") (name "Net-(U21-OUT1)") (class "Default")
      (node (ref "D41") (pin "3") (pinfunction "-_3") (pintype "power_in"))
      (node (ref "U21") (pin "1") (pinfunction "OUT1_1") (pintype "output"))
    )
    (net (code "169") (name "Net-(U21-OUT2)") (class "Default")
      (node (ref "D41") (pin "2") (pinfunction "-_2") (pintype "power_in"))
      (node (ref "U21") (pin "2") (pinfunction "OUT2_2") (pintype "output"))
    )
    (net (code "170") (name "Net-(U21-OUT3)") (class "Default")
      (node (ref "D41") (pin "1") (pinfunction "-_1") (pintype "power_in"))
      (node (ref "U21") (pin "3") (pinfunction "OUT3_3") (pintype "output"))
    )
    (net (code "171") (name "Net-(U21-OUT4)") (class "Default")
      (node (ref "D42") (pin "3") (pinfunction "-_3") (pintype "power_in"))
      (node (ref "U21") (pin "6") (pinfunction "OUT4_6") (pintype "power_in"))
    )
    (net (code "172") (name "Net-(U21-OUT5)") (class "Default")
      (node (ref "D42") (pin "2") (pinfunction "-_2") (pintype "power_in"))
      (node (ref "U21") (pin "7") (pinfunction "OUT5_7") (pintype "output"))
    )
    (net (code "173") (name "Net-(U21-OUT6)") (class "Default")
      (node (ref "D42") (pin "1") (pinfunction "-_1") (pintype "power_in"))
      (node (ref "U21") (pin "8") (pinfunction "OUT6_8") (pintype "output"))
    )
    (net (code "174") (name "Net-(U21-SCLK)") (class "Default")
      (node (ref "U21") (pin "9") (pinfunction "SCLK_9") (pintype "bidirectional"))
      (node (ref "U22") (pin "16") (pinfunction "SCLKI_16") (pintype "bidirectional"))
    )
    (net (code "175") (name "Net-(U21-SD0)") (class "Default")
      (node (ref "U21") (pin "10") (pinfunction "SD0_10") (pintype "bidirectional"))
      (node (ref "U22") (pin "15") (pinfunction "SDI_15") (pintype "bidirectional"))
    )
    (net (code "176") (name "Net-(U22-OUT1)") (class "Default")
      (node (ref "D43") (pin "3") (pinfunction "-_3") (pintype "power_in"))
      (node (ref "U22") (pin "1") (pinfunction "OUT1_1") (pintype "output"))
    )
    (net (code "177") (name "Net-(U22-OUT2)") (class "Default")
      (node (ref "D43") (pin "2") (pinfunction "-_2") (pintype "power_in"))
      (node (ref "U22") (pin "2") (pinfunction "OUT2_2") (pintype "output"))
    )
    (net (code "178") (name "Net-(U22-OUT3)") (class "Default")
      (node (ref "D43") (pin "1") (pinfunction "-_1") (pintype "power_in"))
      (node (ref "U22") (pin "3") (pinfunction "OUT3_3") (pintype "output"))
    )
    (net (code "179") (name "Net-(U22-OUT4)") (class "Default")
      (node (ref "D44") (pin "3") (pinfunction "-_3") (pintype "power_in"))
      (node (ref "U22") (pin "6") (pinfunction "OUT4_6") (pintype "power_in"))
    )
    (net (code "180") (name "Net-(U22-OUT5)") (class "Default")
      (node (ref "D44") (pin "2") (pinfunction "-_2") (pintype "power_in"))
      (node (ref "U22") (pin "7") (pinfunction "OUT5_7") (pintype "output"))
    )
    (net (code "181") (name "Net-(U22-OUT6)") (class "Default")
      (node (ref "D44") (pin "1") (pinfunction "-_1") (pintype "power_in"))
      (node (ref "U22") (pin "8") (pinfunction "OUT6_8") (pintype "output"))
    )
    (net (code "182") (name "Net-(U22-SCLK)") (class "Default")
      (node (ref "U22") (pin "9") (pinfunction "SCLK_9") (pintype "bidirectional"))
      (node (ref "U23") (pin "16") (pinfunction "SCLKI_16") (pintype "bidirectional"))
    )
    (net (code "183") (name "Net-(U22-SD0)") (class "Default")
      (node (ref "U22") (pin "10") (pinfunction "SD0_10") (pintype "bidirectional"))
      (node (ref "U23") (pin "15") (pinfunction "SDI_15") (pintype "bidirectional"))
    )
    (net (code "184") (name "Net-(U23-OUT1)") (class "Default")
      (node (ref "D45") (pin "3") (pinfunction "-_3") (pintype "power_in"))
      (node (ref "U23") (pin "1") (pinfunction "OUT1_1") (pintype "output"))
    )
    (net (code "185") (name "Net-(U23-OUT2)") (class "Default")
      (node (ref "D45") (pin "2") (pinfunction "-_2") (pintype "power_in"))
      (node (ref "U23") (pin "2") (pinfunction "OUT2_2") (pintype "output"))
    )
    (net (code "186") (name "Net-(U23-OUT3)") (class "Default")
      (node (ref "D45") (pin "1") (pinfunction "-_1") (pintype "power_in"))
      (node (ref "U23") (pin "3") (pinfunction "OUT3_3") (pintype "output"))
    )
    (net (code "187") (name "Net-(U23-OUT4)") (class "Default")
      (node (ref "D46") (pin "3") (pinfunction "-_3") (pintype "power_in"))
      (node (ref "U23") (pin "6") (pinfunction "OUT4_6") (pintype "power_in"))
    )
    (net (code "188") (name "Net-(U23-OUT5)") (class "Default")
      (node (ref "D46") (pin "2") (pinfunction "-_2") (pintype "power_in"))
      (node (ref "U23") (pin "7") (pinfunction "OUT5_7") (pintype "output"))
    )
    (net (code "189") (name "Net-(U23-OUT6)") (class "Default")
      (node (ref "D46") (pin "1") (pinfunction "-_1") (pintype "power_in"))
      (node (ref "U23") (pin "8") (pinfunction "OUT6_8") (pintype "output"))
    )
    (net (code "190") (name "Net-(U23-SCLK)") (class "Default")
      (node (ref "U23") (pin "9") (pinfunction "SCLK_9") (pintype "bidirectional"))
      (node (ref "U24") (pin "16") (pinfunction "SCLKI_16") (pintype "bidirectional"))
    )
    (net (code "191") (name "Net-(U23-SD0)") (class "Default")
      (node (ref "U23") (pin "10") (pinfunction "SD0_10") (pintype "bidirectional"))
      (node (ref "U24") (pin "15") (pinfunction "SDI_15") (pintype "bidirectional"))
    )
    (net (code "192") (name "Net-(U24-OUT1)") (class "Default")
      (node (ref "D47") (pin "3") (pinfunction "-_3") (pintype "power_in"))
      (node (ref "U24") (pin "1") (pinfunction "OUT1_1") (pintype "output"))
    )
    (net (code "193") (name "Net-(U24-OUT2)") (class "Default")
      (node (ref "D47") (pin "2") (pinfunction "-_2") (pintype "power_in"))
      (node (ref "U24") (pin "2") (pinfunction "OUT2_2") (pintype "output"))
    )
    (net (code "194") (name "Net-(U24-OUT3)") (class "Default")
      (node (ref "D47") (pin "1") (pinfunction "-_1") (pintype "power_in"))
      (node (ref "U24") (pin "3") (pinfunction "OUT3_3") (pintype "output"))
    )
    (net (code "195") (name "Net-(U24-OUT4)") (class "Default")
      (node (ref "D48") (pin "3") (pinfunction "-_3") (pintype "power_in"))
      (node (ref "U24") (pin "6") (pinfunction "OUT4_6") (pintype "power_in"))
    )
    (net (code "196") (name "Net-(U24-OUT5)") (class "Default")
      (node (ref "D48") (pin "2") (pinfunction "-_2") (pintype "power_in"))
      (node (ref "U24") (pin "7") (pinfunction "OUT5_7") (pintype "output"))
    )
    (net (code "197") (name "Net-(U24-OUT6)") (class "Default")
      (node (ref "D48") (pin "1") (pinfunction "-_1") (pintype "power_in"))
      (node (ref "U24") (pin "8") (pinfunction "OUT6_8") (pintype "output"))
    )
    (net (code "198") (name "Net-(U24-SCLK)") (class "Default")
      (node (ref "U24") (pin "9") (pinfunction "SCLK_9") (pintype "bidirectional"))
      (node (ref "U25") (pin "16") (pinfunction "SCLKI_16") (pintype "bidirectional"))
    )
    (net (code "199") (name "Net-(U24-SD0)") (class "Default")
      (node (ref "U24") (pin "10") (pinfunction "SD0_10") (pintype "bidirectional"))
      (node (ref "U25") (pin "15") (pinfunction "SDI_15") (pintype "bidirectional"))
    )
    (net (code "200") (name "Net-(U25-OUT1)") (class "Default")
      (node (ref "D49") (pin "3") (pinfunction "-_3") (pintype "power_in"))
      (node (ref "U25") (pin "1") (pinfunction "OUT1_1") (pintype "output"))
    )
    (net (code "201") (name "Net-(U25-OUT2)") (class "Default")
      (node (ref "D49") (pin "2") (pinfunction "-_2") (pintype "power_in"))
      (node (ref "U25") (pin "2") (pinfunction "OUT2_2") (pintype "output"))
    )
    (net (code "202") (name "Net-(U25-OUT3)") (class "Default")
      (node (ref "D49") (pin "1") (pinfunction "-_1") (pintype "power_in"))
      (node (ref "U25") (pin "3") (pinfunction "OUT3_3") (pintype "output"))
    )
    (net (code "203") (name "Net-(U25-OUT4)") (class "Default")
      (node (ref "D50") (pin "3") (pinfunction "-_3") (pintype "power_in"))
      (node (ref "U25") (pin "6") (pinfunction "OUT4_6") (pintype "power_in"))
    )
    (net (code "204") (name "Net-(U25-OUT5)") (class "Default")
      (node (ref "D50") (pin "2") (pinfunction "-_2") (pintype "power_in"))
      (node (ref "U25") (pin "7") (pinfunction "OUT5_7") (pintype "output"))
    )
    (net (code "205") (name "Net-(U25-OUT6)") (class "Default")
      (node (ref "D50") (pin "1") (pinfunction "-_1") (pintype "power_in"))
      (node (ref "U25") (pin "8") (pinfunction "OUT6_8") (pintype "output"))
    )
    (net (code "206") (name "Net-(U25-SCLK)") (class "Default")
      (node (ref "U25") (pin "9") (pinfunction "SCLK_9") (pintype "bidirectional"))
      (node (ref "U26") (pin "16") (pinfunction "SCLKI_16") (pintype "bidirectional"))
    )
    (net (code "207") (name "Net-(U25-SD0)") (class "Default")
      (node (ref "U25") (pin "10") (pinfunction "SD0_10") (pintype "bidirectional"))
      (node (ref "U26") (pin "15") (pinfunction "SDI_15") (pintype "bidirectional"))
    )
    (net (code "208") (name "Net-(U26-OUT1)") (class "Default")
      (node (ref "D51") (pin "3") (pinfunction "-_3") (pintype "power_in"))
      (node (ref "U26") (pin "1") (pinfunction "OUT1_1") (pintype "output"))
    )
    (net (code "209") (name "Net-(U26-OUT2)") (class "Default")
      (node (ref "D51") (pin "2") (pinfunction "-_2") (pintype "power_in"))
      (node (ref "U26") (pin "2") (pinfunction "OUT2_2") (pintype "output"))
    )
    (net (code "210") (name "Net-(U26-OUT3)") (class "Default")
      (node (ref "D51") (pin "1") (pinfunction "-_1") (pintype "power_in"))
      (node (ref "U26") (pin "3") (pinfunction "OUT3_3") (pintype "output"))
    )
    (net (code "211") (name "Net-(U26-OUT4)") (class "Default")
      (node (ref "D52") (pin "3") (pinfunction "-_3") (pintype "power_in"))
      (node (ref "U26") (pin "6") (pinfunction "OUT4_6") (pintype "power_in"))
    )
    (net (code "212") (name "Net-(U26-OUT5)") (class "Default")
      (node (ref "D52") (pin "2") (pinfunction "-_2") (pintype "power_in"))
      (node (ref "U26") (pin "7") (pinfunction "OUT5_7") (pintype "output"))
    )
    (net (code "213") (name "Net-(U26-OUT6)") (class "Default")
      (node (ref "D52") (pin "1") (pinfunction "-_1") (pintype "power_in"))
      (node (ref "U26") (pin "8") (pinfunction "OUT6_8") (pintype "output"))
    )
    (net (code "214") (name "Net-(U26-SCLK)") (class "Default")
      (node (ref "U26") (pin "9") (pinfunction "SCLK_9") (pintype "bidirectional"))
      (node (ref "U27") (pin "16") (pinfunction "SCLKI_16") (pintype "bidirectional"))
    )
    (net (code "215") (name "Net-(U26-SD0)") (class "Default")
      (node (ref "U26") (pin "10") (pinfunction "SD0_10") (pintype "bidirectional"))
      (node (ref "U27") (pin "15") (pinfunction "SDI_15") (pintype "bidirectional"))
    )
    (net (code "216") (name "Net-(U27-OUT1)") (class "Default")
      (node (ref "D53") (pin "3") (pinfunction "-_3") (pintype "power_in"))
      (node (ref "U27") (pin "1") (pinfunction "OUT1_1") (pintype "output"))
    )
    (net (code "217") (name "Net-(U27-OUT2)") (class "Default")
      (node (ref "D53") (pin "2") (pinfunction "-_2") (pintype "power_in"))
      (node (ref "U27") (pin "2") (pinfunction "OUT2_2") (pintype "output"))
    )
    (net (code "218") (name "Net-(U27-OUT3)") (class "Default")
      (node (ref "D53") (pin "1") (pinfunction "-_1") (pintype "power_in"))
      (node (ref "U27") (pin "3") (pinfunction "OUT3_3") (pintype "output"))
    )
    (net (code "219") (name "Net-(U27-OUT4)") (class "Default")
      (node (ref "D54") (pin "3") (pinfunction "-_3") (pintype "power_in"))
      (node (ref "U27") (pin "6") (pinfunction "OUT4_6") (pintype "power_in"))
    )
    (net (code "220") (name "Net-(U27-OUT5)") (class "Default")
      (node (ref "D54") (pin "2") (pinfunction "-_2") (pintype "power_in"))
      (node (ref "U27") (pin "7") (pinfunction "OUT5_7") (pintype "output"))
    )
    (net (code "221") (name "Net-(U27-OUT6)") (class "Default")
      (node (ref "D54") (pin "1") (pinfunction "-_1") (pintype "power_in"))
      (node (ref "U27") (pin "8") (pinfunction "OUT6_8") (pintype "output"))
    )
    (net (code "222") (name "Net-(U27-SCLK)") (class "Default")
      (node (ref "U27") (pin "9") (pinfunction "SCLK_9") (pintype "bidirectional"))
      (node (ref "U28") (pin "16") (pinfunction "SCLKI_16") (pintype "bidirectional"))
    )
    (net (code "223") (name "Net-(U27-SD0)") (class "Default")
      (node (ref "U27") (pin "10") (pinfunction "SD0_10") (pintype "bidirectional"))
      (node (ref "U28") (pin "15") (pinfunction "SDI_15") (pintype "bidirectional"))
    )
    (net (code "224") (name "Net-(U28-OUT1)") (class "Default")
      (node (ref "D55") (pin "3") (pinfunction "-_3") (pintype "power_in"))
      (node (ref "U28") (pin "1") (pinfunction "OUT1_1") (pintype "output"))
    )
    (net (code "225") (name "Net-(U28-OUT2)") (class "Default")
      (node (ref "D55") (pin "2") (pinfunction "-_2") (pintype "power_in"))
      (node (ref "U28") (pin "2") (pinfunction "OUT2_2") (pintype "output"))
    )
    (net (code "226") (name "Net-(U28-OUT3)") (class "Default")
      (node (ref "D55") (pin "1") (pinfunction "-_1") (pintype "power_in"))
      (node (ref "U28") (pin "3") (pinfunction "OUT3_3") (pintype "output"))
    )
    (net (code "227") (name "Net-(U28-OUT4)") (class "Default")
      (node (ref "D56") (pin "3") (pinfunction "-_3") (pintype "power_in"))
      (node (ref "U28") (pin "6") (pinfunction "OUT4_6") (pintype "power_in"))
    )
    (net (code "228") (name "Net-(U28-OUT5)") (class "Default")
      (node (ref "D56") (pin "2") (pinfunction "-_2") (pintype "power_in"))
      (node (ref "U28") (pin "7") (pinfunction "OUT5_7") (pintype "output"))
    )
    (net (code "229") (name "Net-(U28-OUT6)") (class "Default")
      (node (ref "D56") (pin "1") (pinfunction "-_1") (pintype "power_in"))
      (node (ref "U28") (pin "8") (pinfunction "OUT6_8") (pintype "output"))
    )
    (net (code "230") (name "Net-(U28-SCLK)") (class "Default")
      (node (ref "U28") (pin "9") (pinfunction "SCLK_9") (pintype "bidirectional"))
      (node (ref "U29") (pin "16") (pinfunction "SCLKI_16") (pintype "bidirectional"))
    )
    (net (code "231") (name "Net-(U28-SD0)") (class "Default")
      (node (ref "U28") (pin "10") (pinfunction "SD0_10") (pintype "bidirectional"))
      (node (ref "U29") (pin "15") (pinfunction "SDI_15") (pintype "bidirectional"))
    )
    (net (code "232") (name "Net-(U29-OUT1)") (class "Default")
      (node (ref "D57") (pin "3") (pinfunction "-_3") (pintype "power_in"))
      (node (ref "U29") (pin "1") (pinfunction "OUT1_1") (pintype "output"))
    )
    (net (code "233") (name "Net-(U29-OUT2)") (class "Default")
      (node (ref "D57") (pin "2") (pinfunction "-_2") (pintype "power_in"))
      (node (ref "U29") (pin "2") (pinfunction "OUT2_2") (pintype "output"))
    )
    (net (code "234") (name "Net-(U29-OUT3)") (class "Default")
      (node (ref "D57") (pin "1") (pinfunction "-_1") (pintype "power_in"))
      (node (ref "U29") (pin "3") (pinfunction "OUT3_3") (pintype "output"))
    )
    (net (code "235") (name "Net-(U29-OUT4)") (class "Default")
      (node (ref "D58") (pin "3") (pinfunction "-_3") (pintype "power_in"))
      (node (ref "U29") (pin "6") (pinfunction "OUT4_6") (pintype "power_in"))
    )
    (net (code "236") (name "Net-(U29-OUT5)") (class "Default")
      (node (ref "D58") (pin "2") (pinfunction "-_2") (pintype "power_in"))
      (node (ref "U29") (pin "7") (pinfunction "OUT5_7") (pintype "output"))
    )
    (net (code "237") (name "Net-(U29-OUT6)") (class "Default")
      (node (ref "D58") (pin "1") (pinfunction "-_1") (pintype "power_in"))
      (node (ref "U29") (pin "8") (pinfunction "OUT6_8") (pintype "output"))
    )
    (net (code "238") (name "Net-(U29-SCLK)") (class "Default")
      (node (ref "U29") (pin "9") (pinfunction "SCLK_9") (pintype "bidirectional"))
      (node (ref "U30") (pin "16") (pinfunction "SCLKI_16") (pintype "bidirectional"))
    )
    (net (code "239") (name "Net-(U29-SD0)") (class "Default")
      (node (ref "U29") (pin "10") (pinfunction "SD0_10") (pintype "bidirectional"))
      (node (ref "U30") (pin "15") (pinfunction "SDI_15") (pintype "bidirectional"))
    )
    (net (code "240") (name "Net-(U30-OUT1)") (class "Default")
      (node (ref "D59") (pin "3") (pinfunction "-_3") (pintype "power_in"))
      (node (ref "U30") (pin "1") (pinfunction "OUT1_1") (pintype "output"))
    )
    (net (code "241") (name "Net-(U30-OUT2)") (class "Default")
      (node (ref "D59") (pin "2") (pinfunction "-_2") (pintype "power_in"))
      (node (ref "U30") (pin "2") (pinfunction "OUT2_2") (pintype "output"))
    )
    (net (code "242") (name "Net-(U30-OUT3)") (class "Default")
      (node (ref "D59") (pin "1") (pinfunction "-_1") (pintype "power_in"))
      (node (ref "U30") (pin "3") (pinfunction "OUT3_3") (pintype "output"))
    )
    (net (code "243") (name "Net-(U30-OUT4)") (class "Default")
      (node (ref "D60") (pin "3") (pinfunction "-_3") (pintype "power_in"))
      (node (ref "U30") (pin "6") (pinfunction "OUT4_6") (pintype "power_in"))
    )
    (net (code "244") (name "Net-(U30-OUT5)") (class "Default")
      (node (ref "D60") (pin "2") (pinfunction "-_2") (pintype "power_in"))
      (node (ref "U30") (pin "7") (pinfunction "OUT5_7") (pintype "output"))
    )
    (net (code "245") (name "Net-(U30-OUT6)") (class "Default")
      (node (ref "D60") (pin "1") (pinfunction "-_1") (pintype "power_in"))
      (node (ref "U30") (pin "8") (pinfunction "OUT6_8") (pintype "output"))
    )
    (net (code "246") (name "unconnected-(U1-NC-Pad12)") (class "Default")
      (node (ref "U1") (pin "12") (pinfunction "NC_12") (pintype "passive+no_connect"))
    )
    (net (code "247") (name "unconnected-(U1-OMODE-Pad11)") (class "Default")
      (node (ref "U1") (pin "11") (pinfunction "OMODE_11") (pintype "bidirectional+no_connect"))
    )
    (net (code "248") (name "unconnected-(U1-PMODE-Pad14)") (class "Default")
      (node (ref "U1") (pin "14") (pinfunction "PMODE_14") (pintype "bidirectional+no_connect"))
    )
    (net (code "249") (name "unconnected-(U2-NC-Pad12)") (class "Default")
      (node (ref "U2") (pin "12") (pinfunction "NC_12") (pintype "passive+no_connect"))
    )
    (net (code "250") (name "unconnected-(U2-OMODE-Pad11)") (class "Default")
      (node (ref "U2") (pin "11") (pinfunction "OMODE_11") (pintype "bidirectional+no_connect"))
    )
    (net (code "251") (name "unconnected-(U2-PMODE-Pad14)") (class "Default")
      (node (ref "U2") (pin "14") (pinfunction "PMODE_14") (pintype "bidirectional+no_connect"))
    )
    (net (code "252") (name "unconnected-(U3-NC-Pad12)") (class "Default")
      (node (ref "U3") (pin "12") (pinfunction "NC_12") (pintype "passive+no_connect"))
    )
    (net (code "253") (name "unconnected-(U3-OMODE-Pad11)") (class "Default")
      (node (ref "U3") (pin "11") (pinfunction "OMODE_11") (pintype "bidirectional+no_connect"))
    )
    (net (code "254") (name "unconnected-(U3-PMODE-Pad14)") (class "Default")
      (node (ref "U3") (pin "14") (pinfunction "PMODE_14") (pintype "bidirectional+no_connect"))
    )
    (net (code "255") (name "unconnected-(U4-NC-Pad12)") (class "Default")
      (node (ref "U4") (pin "12") (pinfunction "NC_12") (pintype "passive+no_connect"))
    )
    (net (code "256") (name "unconnected-(U4-OMODE-Pad11)") (class "Default")
      (node (ref "U4") (pin "11") (pinfunction "OMODE_11") (pintype "bidirectional+no_connect"))
    )
    (net (code "257") (name "unconnected-(U4-PMODE-Pad14)") (class "Default")
      (node (ref "U4") (pin "14") (pinfunction "PMODE_14") (pintype "bidirectional+no_connect"))
    )
    (net (code "258") (name "unconnected-(U5-NC-Pad12)") (class "Default")
      (node (ref "U5") (pin "12") (pinfunction "NC_12") (pintype "passive+no_connect"))
    )
    (net (code "259") (name "unconnected-(U5-OMODE-Pad11)") (class "Default")
      (node (ref "U5") (pin "11") (pinfunction "OMODE_11") (pintype "bidirectional+no_connect"))
    )
    (net (code "260") (name "unconnected-(U5-PMODE-Pad14)") (class "Default")
      (node (ref "U5") (pin "14") (pinfunction "PMODE_14") (pintype "bidirectional+no_connect"))
    )
    (net (code "261") (name "unconnected-(U6-NC-Pad12)") (class "Default")
      (node (ref "U6") (pin "12") (pinfunction "NC_12") (pintype "passive+no_connect"))
    )
    (net (code "262") (name "unconnected-(U6-OMODE-Pad11)") (class "Default")
      (node (ref "U6") (pin "11") (pinfunction "OMODE_11") (pintype "bidirectional+no_connect"))
    )
    (net (code "263") (name "unconnected-(U6-PMODE-Pad14)") (class "Default")
      (node (ref "U6") (pin "14") (pinfunction "PMODE_14") (pintype "bidirectional+no_connect"))
    )
    (net (code "264") (name "unconnected-(U7-NC-Pad12)") (class "Default")
      (node (ref "U7") (pin "12") (pinfunction "NC_12") (pintype "passive+no_connect"))
    )
    (net (code "265") (name "unconnected-(U7-OMODE-Pad11)") (class "Default")
      (node (ref "U7") (pin "11") (pinfunction "OMODE_11") (pintype "bidirectional+no_connect"))
    )
    (net (code "266") (name "unconnected-(U7-PMODE-Pad14)") (class "Default")
      (node (ref "U7") (pin "14") (pinfunction "PMODE_14") (pintype "bidirectional+no_connect"))
    )
    (net (code "267") (name "unconnected-(U8-NC-Pad12)") (class "Default")
      (node (ref "U8") (pin "12") (pinfunction "NC_12") (pintype "passive+no_connect"))
    )
    (net (code "268") (name "unconnected-(U8-OMODE-Pad11)") (class "Default")
      (node (ref "U8") (pin "11") (pinfunction "OMODE_11") (pintype "bidirectional+no_connect"))
    )
    (net (code "269") (name "unconnected-(U8-PMODE-Pad14)") (class "Default")
      (node (ref "U8") (pin "14") (pinfunction "PMODE_14") (pintype "bidirectional+no_connect"))
    )
    (net (code "270") (name "unconnected-(U9-NC-Pad12)") (class "Default")
      (node (ref "U9") (pin "12") (pinfunction "NC_12") (pintype "passive+no_connect"))
    )
    (net (code "271") (name "unconnected-(U9-OMODE-Pad11)") (class "Default")
      (node (ref "U9") (pin "11") (pinfunction "OMODE_11") (pintype "bidirectional+no_connect"))
    )
    (net (code "272") (name "unconnected-(U9-PMODE-Pad14)") (class "Default")
      (node (ref "U9") (pin "14") (pinfunction "PMODE_14") (pintype "bidirectional+no_connect"))
    )
    (net (code "273") (name "unconnected-(U10-NC-Pad12)") (class "Default")
      (node (ref "U10") (pin "12") (pinfunction "NC_12") (pintype "passive+no_connect"))
    )
    (net (code "274") (name "unconnected-(U10-OMODE-Pad11)") (class "Default")
      (node (ref "U10") (pin "11") (pinfunction "OMODE_11") (pintype "bidirectional+no_connect"))
    )
    (net (code "275") (name "unconnected-(U10-PMODE-Pad14)") (class "Default")
      (node (ref "U10") (pin "14") (pinfunction "PMODE_14") (pintype "bidirectional+no_connect"))
    )
    (net (code "276") (name "unconnected-(U11-NC-Pad12)") (class "Default")
      (node (ref "U11") (pin "12") (pinfunction "NC_12") (pintype "passive+no_connect"))
    )
    (net (code "277") (name "unconnected-(U11-OMODE-Pad11)") (class "Default")
      (node (ref "U11") (pin "11") (pinfunction "OMODE_11") (pintype "bidirectional+no_connect"))
    )
    (net (code "278") (name "unconnected-(U11-PMODE-Pad14)") (class "Default")
      (node (ref "U11") (pin "14") (pinfunction "PMODE_14") (pintype "bidirectional+no_connect"))
    )
    (net (code "279") (name "unconnected-(U12-NC-Pad12)") (class "Default")
      (node (ref "U12") (pin "12") (pinfunction "NC_12") (pintype "passive+no_connect"))
    )
    (net (code "280") (name "unconnected-(U12-OMODE-Pad11)") (class "Default")
      (node (ref "U12") (pin "11") (pinfunction "OMODE_11") (pintype "bidirectional+no_connect"))
    )
    (net (code "281") (name "unconnected-(U12-PMODE-Pad14)") (class "Default")
      (node (ref "U12") (pin "14") (pinfunction "PMODE_14") (pintype "bidirectional+no_connect"))
    )
    (net (code "282") (name "unconnected-(U13-NC-Pad12)") (class "Default")
      (node (ref "U13") (pin "12") (pinfunction "NC_12") (pintype "passive+no_connect"))
    )
    (net (code "283") (name "unconnected-(U13-OMODE-Pad11)") (class "Default")
      (node (ref "U13") (pin "11") (pinfunction "OMODE_11") (pintype "bidirectional+no_connect"))
    )
    (net (code "284") (name "unconnected-(U13-PMODE-Pad14)") (class "Default")
      (node (ref "U13") (pin "14") (pinfunction "PMODE_14") (pintype "bidirectional+no_connect"))
    )
    (net (code "285") (name "unconnected-(U14-NC-Pad12)") (class "Default")
      (node (ref "U14") (pin "12") (pinfunction "NC_12") (pintype "passive+no_connect"))
    )
    (net (code "286") (name "unconnected-(U14-OMODE-Pad11)") (class "Default")
      (node (ref "U14") (pin "11") (pinfunction "OMODE_11") (pintype "bidirectional+no_connect"))
    )
    (net (code "287") (name "unconnected-(U14-PMODE-Pad14)") (class "Default")
      (node (ref "U14") (pin "14") (pinfunction "PMODE_14") (pintype "bidirectional+no_connect"))
    )
    (net (code "288") (name "unconnected-(U15-NC-Pad12)") (class "Default")
      (node (ref "U15") (pin "12") (pinfunction "NC_12") (pintype "passive+no_connect"))
    )
    (net (code "289") (name "unconnected-(U15-OMODE-Pad11)") (class "Default")
      (node (ref "U15") (pin "11") (pinfunction "OMODE_11") (pintype "bidirectional+no_connect"))
    )
    (net (code "290") (name "unconnected-(U15-PMODE-Pad14)") (class "Default")
      (node (ref "U15") (pin "14") (pinfunction "PMODE_14") (pintype "bidirectional+no_connect"))
    )
    (net (code "291") (name "unconnected-(U16-NC-Pad12)") (class "Default")
      (node (ref "U16") (pin "12") (pinfunction "NC_12") (pintype "passive+no_connect"))
    )
    (net (code "292") (name "unconnected-(U16-OMODE-Pad11)") (class "Default")
      (node (ref "U16") (pin "11") (pinfunction "OMODE_11") (pintype "bidirectional+no_connect"))
    )
    (net (code "293") (name "unconnected-(U16-PMODE-Pad14)") (class "Default")
      (node (ref "U16") (pin "14") (pinfunction "PMODE_14") (pintype "bidirectional+no_connect"))
    )
    (net (code "294") (name "unconnected-(U17-NC-Pad12)") (class "Default")
      (node (ref "U17") (pin "12") (pinfunction "NC_12") (pintype "passive+no_connect"))
    )
    (net (code "295") (name "unconnected-(U17-OMODE-Pad11)") (class "Default")
      (node (ref "U17") (pin "11") (pinfunction "OMODE_11") (pintype "bidirectional+no_connect"))
    )
    (net (code "296") (name "unconnected-(U17-PMODE-Pad14)") (class "Default")
      (node (ref "U17") (pin "14") (pinfunction "PMODE_14") (pintype "bidirectional+no_connect"))
    )
    (net (code "297") (name "unconnected-(U18-NC-Pad12)") (class "Default")
      (node (ref "U18") (pin "12") (pinfunction "NC_12") (pintype "passive+no_connect"))
    )
    (net (code "298") (name "unconnected-(U18-OMODE-Pad11)") (class "Default")
      (node (ref "U18") (pin "11") (pinfunction "OMODE_11") (pintype "bidirectional+no_connect"))
    )
    (net (code "299") (name "unconnected-(U18-PMODE-Pad14)") (class "Default")
      (node (ref "U18") (pin "14") (pinfunction "PMODE_14") (pintype "bidirectional+no_connect"))
    )
    (net (code "300") (name "unconnected-(U19-NC-Pad12)") (class "Default")
      (node (ref "U19") (pin "12") (pinfunction "NC_12") (pintype "passive+no_connect"))
    )
    (net (code "301") (name "unconnected-(U19-OMODE-Pad11)") (class "Default")
      (node (ref "U19") (pin "11") (pinfunction "OMODE_11") (pintype "bidirectional+no_connect"))
    )
    (net (code "302") (name "unconnected-(U19-PMODE-Pad14)") (class "Default")
      (node (ref "U19") (pin "14") (pinfunction "PMODE_14") (pintype "bidirectional+no_connect"))
    )
    (net (code "303") (name "unconnected-(U20-NC-Pad12)") (class "Default")
      (node (ref "U20") (pin "12") (pinfunction "NC_12") (pintype "passive+no_connect"))
    )
    (net (code "304") (name "unconnected-(U20-OMODE-Pad11)") (class "Default")
      (node (ref "U20") (pin "11") (pinfunction "OMODE_11") (pintype "bidirectional+no_connect"))
    )
    (net (code "305") (name "unconnected-(U20-PMODE-Pad14)") (class "Default")
      (node (ref "U20") (pin "14") (pinfunction "PMODE_14") (pintype "bidirectional+no_connect"))
    )
    (net (code "306") (name "unconnected-(U21-NC-Pad12)") (class "Default")
      (node (ref "U21") (pin "12") (pinfunction "NC_12") (pintype "passive+no_connect"))
    )
    (net (code "307") (name "unconnected-(U21-OMODE-Pad11)") (class "Default")
      (node (ref "U21") (pin "11") (pinfunction "OMODE_11") (pintype "bidirectional+no_connect"))
    )
    (net (code "308") (name "unconnected-(U21-PMODE-Pad14)") (class "Default")
      (node (ref "U21") (pin "14") (pinfunction "PMODE_14") (pintype "bidirectional+no_connect"))
    )
    (net (code "309") (name "unconnected-(U22-NC-Pad12)") (class "Default")
      (node (ref "U22") (pin "12") (pinfunction "NC_12") (pintype "passive+no_connect"))
    )
    (net (code "310") (name "unconnected-(U22-OMODE-Pad11)") (class "Default")
      (node (ref "U22") (pin "11") (pinfunction "OMODE_11") (pintype "bidirectional+no_connect"))
    )
    (net (code "311") (name "unconnected-(U22-PMODE-Pad14)") (class "Default")
      (node (ref "U22") (pin "14") (pinfunction "PMODE_14") (pintype "bidirectional+no_connect"))
    )
    (net (code "312") (name "unconnected-(U23-NC-Pad12)") (class "Default")
      (node (ref "U23") (pin "12") (pinfunction "NC_12") (pintype "passive+no_connect"))
    )
    (net (code "313") (name "unconnected-(U23-OMODE-Pad11)") (class "Default")
      (node (ref "U23") (pin "11") (pinfunction "OMODE_11") (pintype "bidirectional+no_connect"))
    )
    (net (code "314") (name "unconnected-(U23-PMODE-Pad14)") (class "Default")
      (node (ref "U23") (pin "14") (pinfunction "PMODE_14") (pintype "bidirectional+no_connect"))
    )
    (net (code "315") (name "unconnected-(U24-NC-Pad12)") (class "Default")
      (node (ref "U24") (pin "12") (pinfunction "NC_12") (pintype "passive+no_connect"))
    )
    (net (code "316") (name "unconnected-(U24-OMODE-Pad11)") (class "Default")
      (node (ref "U24") (pin "11") (pinfunction "OMODE_11") (pintype "bidirectional+no_connect"))
    )
    (net (code "317") (name "unconnected-(U24-PMODE-Pad14)") (class "Default")
      (node (ref "U24") (pin "14") (pinfunction "PMODE_14") (pintype "bidirectional+no_connect"))
    )
    (net (code "318") (name "unconnected-(U25-NC-Pad12)") (class "Default")
      (node (ref "U25") (pin "12") (pinfunction "NC_12") (pintype "passive+no_connect"))
    )
    (net (code "319") (name "unconnected-(U25-OMODE-Pad11)") (class "Default")
      (node (ref "U25") (pin "11") (pinfunction "OMODE_11") (pintype "bidirectional+no_connect"))
    )
    (net (code "320") (name "unconnected-(U25-PMODE-Pad14)") (class "Default")
      (node (ref "U25") (pin "14") (pinfunction "PMODE_14") (pintype "bidirectional+no_connect"))
    )
    (net (code "321") (name "unconnected-(U26-NC-Pad12)") (class "Default")
      (node (ref "U26") (pin "12") (pinfunction "NC_12") (pintype "passive+no_connect"))
    )
    (net (code "322") (name "unconnected-(U26-OMODE-Pad11)") (class "Default")
      (node (ref "U26") (pin "11") (pinfunction "OMODE_11") (pintype "bidirectional+no_connect"))
    )
    (net (code "323") (name "unconnected-(U26-PMODE-Pad14)") (class "Default")
      (node (ref "U26") (pin "14") (pinfunction "PMODE_14") (pintype "bidirectional+no_connect"))
    )
    (net (code "324") (name "unconnected-(U27-NC-Pad12)") (class "Default")
      (node (ref "U27") (pin "12") (pinfunction "NC_12") (pintype "passive+no_connect"))
    )
    (net (code "325") (name "unconnected-(U27-OMODE-Pad11)") (class "Default")
      (node (ref "U27") (pin "11") (pinfunction "OMODE_11") (pintype "bidirectional+no_connect"))
    )
    (net (code "326") (name "unconnected-(U27-PMODE-Pad14)") (class "Default")
      (node (ref "U27") (pin "14") (pinfunction "PMODE_14") (pintype "bidirectional+no_connect"))
    )
    (net (code "327") (name "unconnected-(U28-NC-Pad12)") (class "Default")
      (node (ref "U28") (pin "12") (pinfunction "NC_12") (pintype "passive+no_connect"))
    )
    (net (code "328") (name "unconnected-(U28-OMODE-Pad11)") (class "Default")
      (node (ref "U28") (pin "11") (pinfunction "OMODE_11") (pintype "bidirectional+no_connect"))
    )
    (net (code "329") (name "unconnected-(U28-PMODE-Pad14)") (class "Default")
      (node (ref "U28") (pin "14") (pinfunction "PMODE_14") (pintype "bidirectional+no_connect"))
    )
    (net (code "330") (name "unconnected-(U29-NC-Pad12)") (class "Default")
      (node (ref "U29") (pin "12") (pinfunction "NC_12") (pintype "passive+no_connect"))
    )
    (net (code "331") (name "unconnected-(U29-OMODE-Pad11)") (class "Default")
      (node (ref "U29") (pin "11") (pinfunction "OMODE_11") (pintype "bidirectional+no_connect"))
    )
    (net (code "332") (name "unconnected-(U29-PMODE-Pad14)") (class "Default")
      (node (ref "U29") (pin "14") (pinfunction "PMODE_14") (pintype "bidirectional+no_connect"))
    )
    (net (code "333") (name "unconnected-(U30-NC-Pad12)") (class "Default")
      (node (ref "U30") (pin "12") (pinfunction "NC_12") (pintype "passive+no_connect"))
    )
    (net (code "334") (name "unconnected-(U30-OMODE-Pad11)") (class "Default")
      (node (ref "U30") (pin "11") (pinfunction "OMODE_11") (pintype "bidirectional+no_connect"))
    )
    (net (code "335") (name "unconnected-(U30-PMODE-Pad14)") (class "Default")
      (node (ref "U30") (pin "14") (pinfunction "PMODE_14") (pintype "bidirectional+no_connect"))
    )
  )
)
